# Ucus_Kontrol_Bilgisayari.net
KiCad netlist of a schematic drawn in Altium Designer
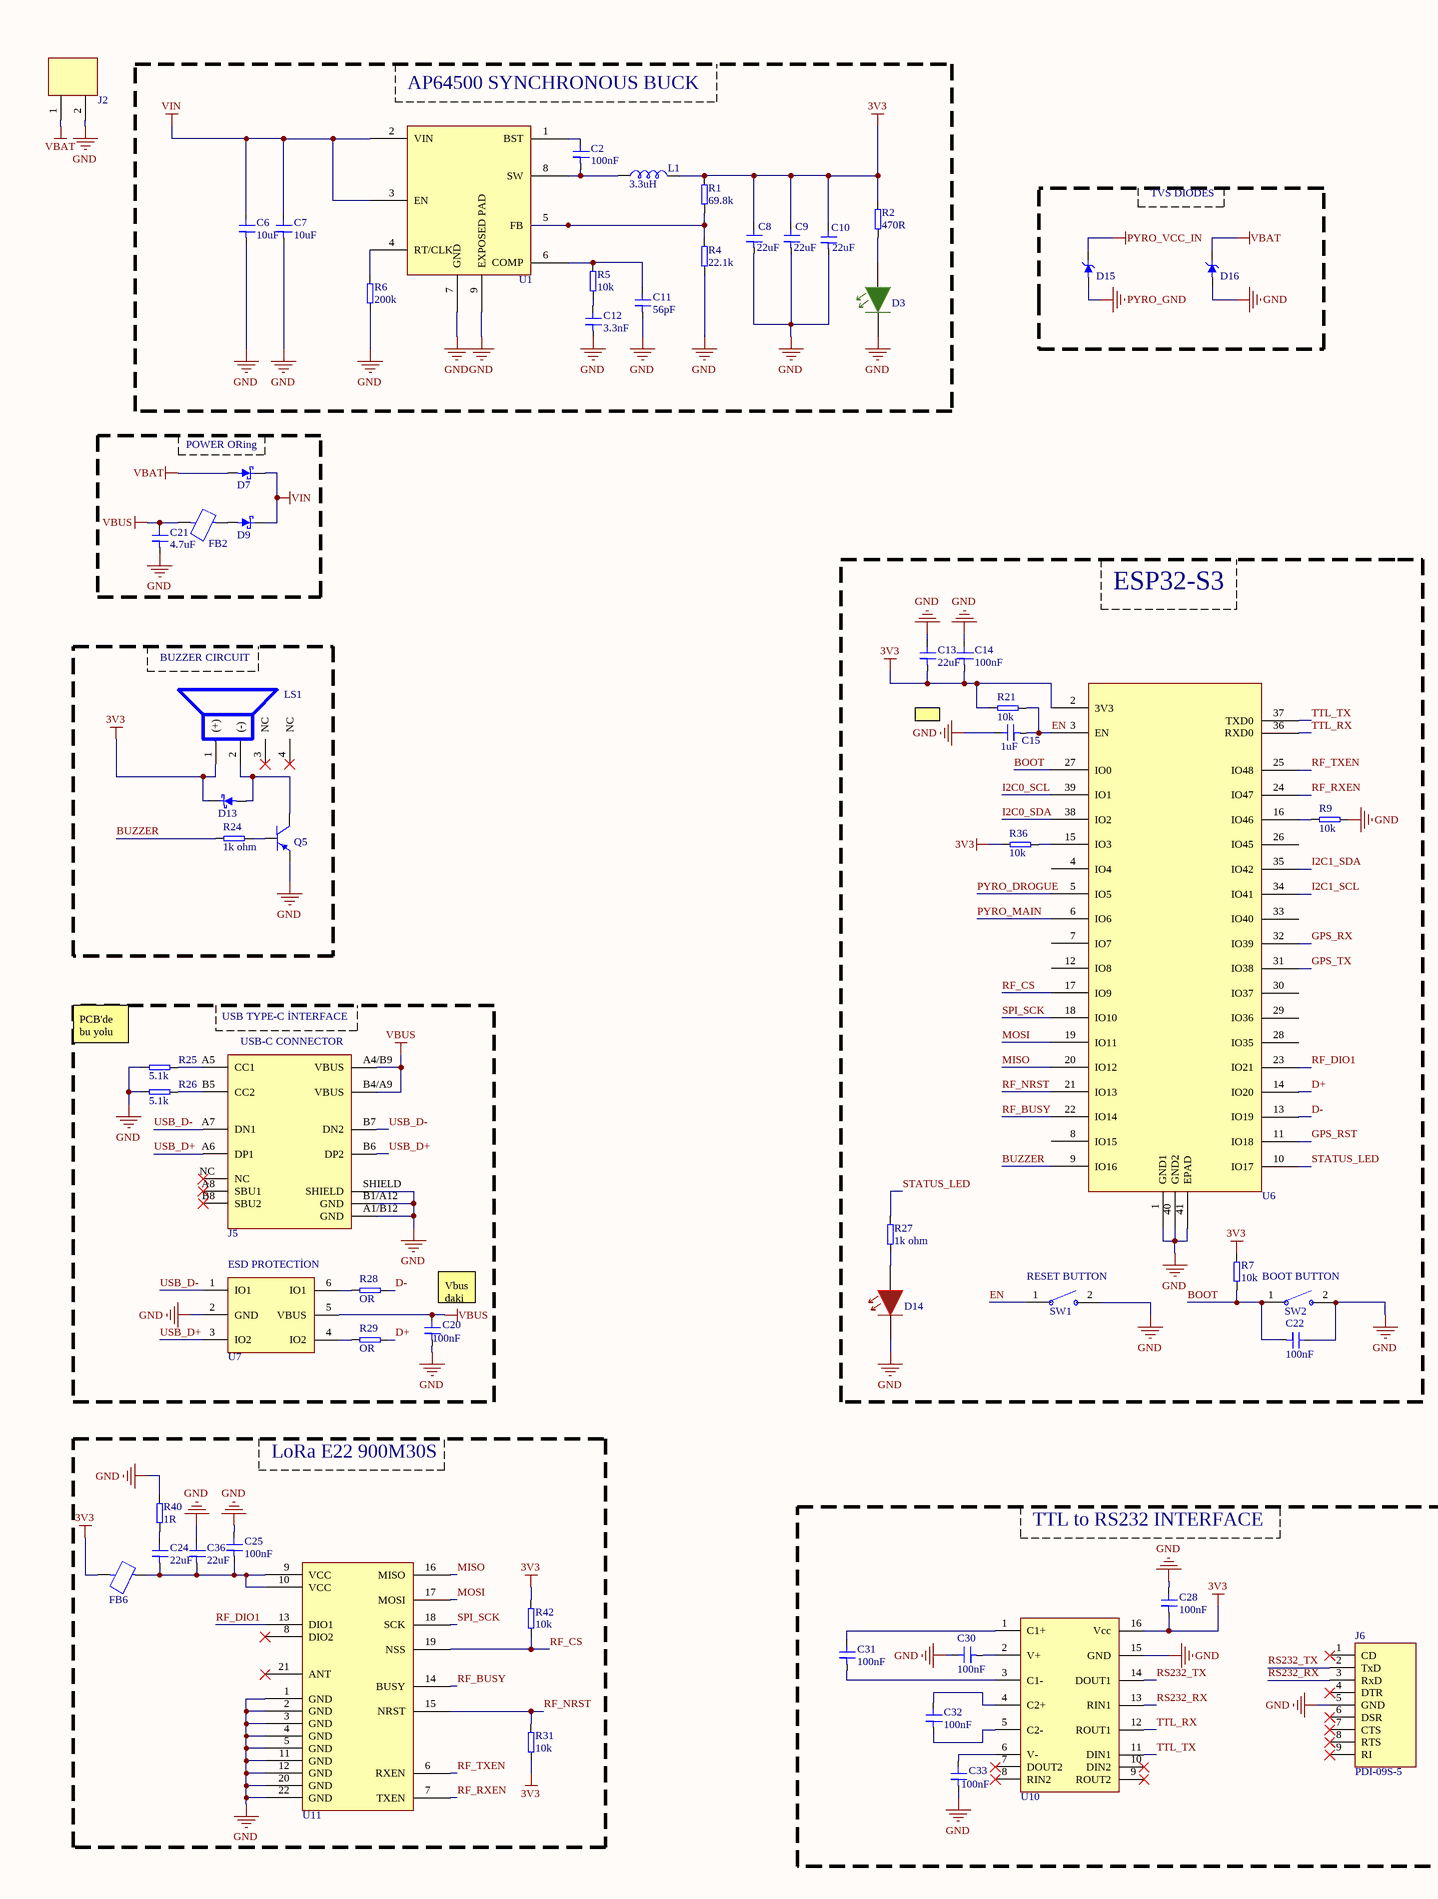
[diagram p0: Ucus_Kontrol_Bilgisayari.SchDoc, left]
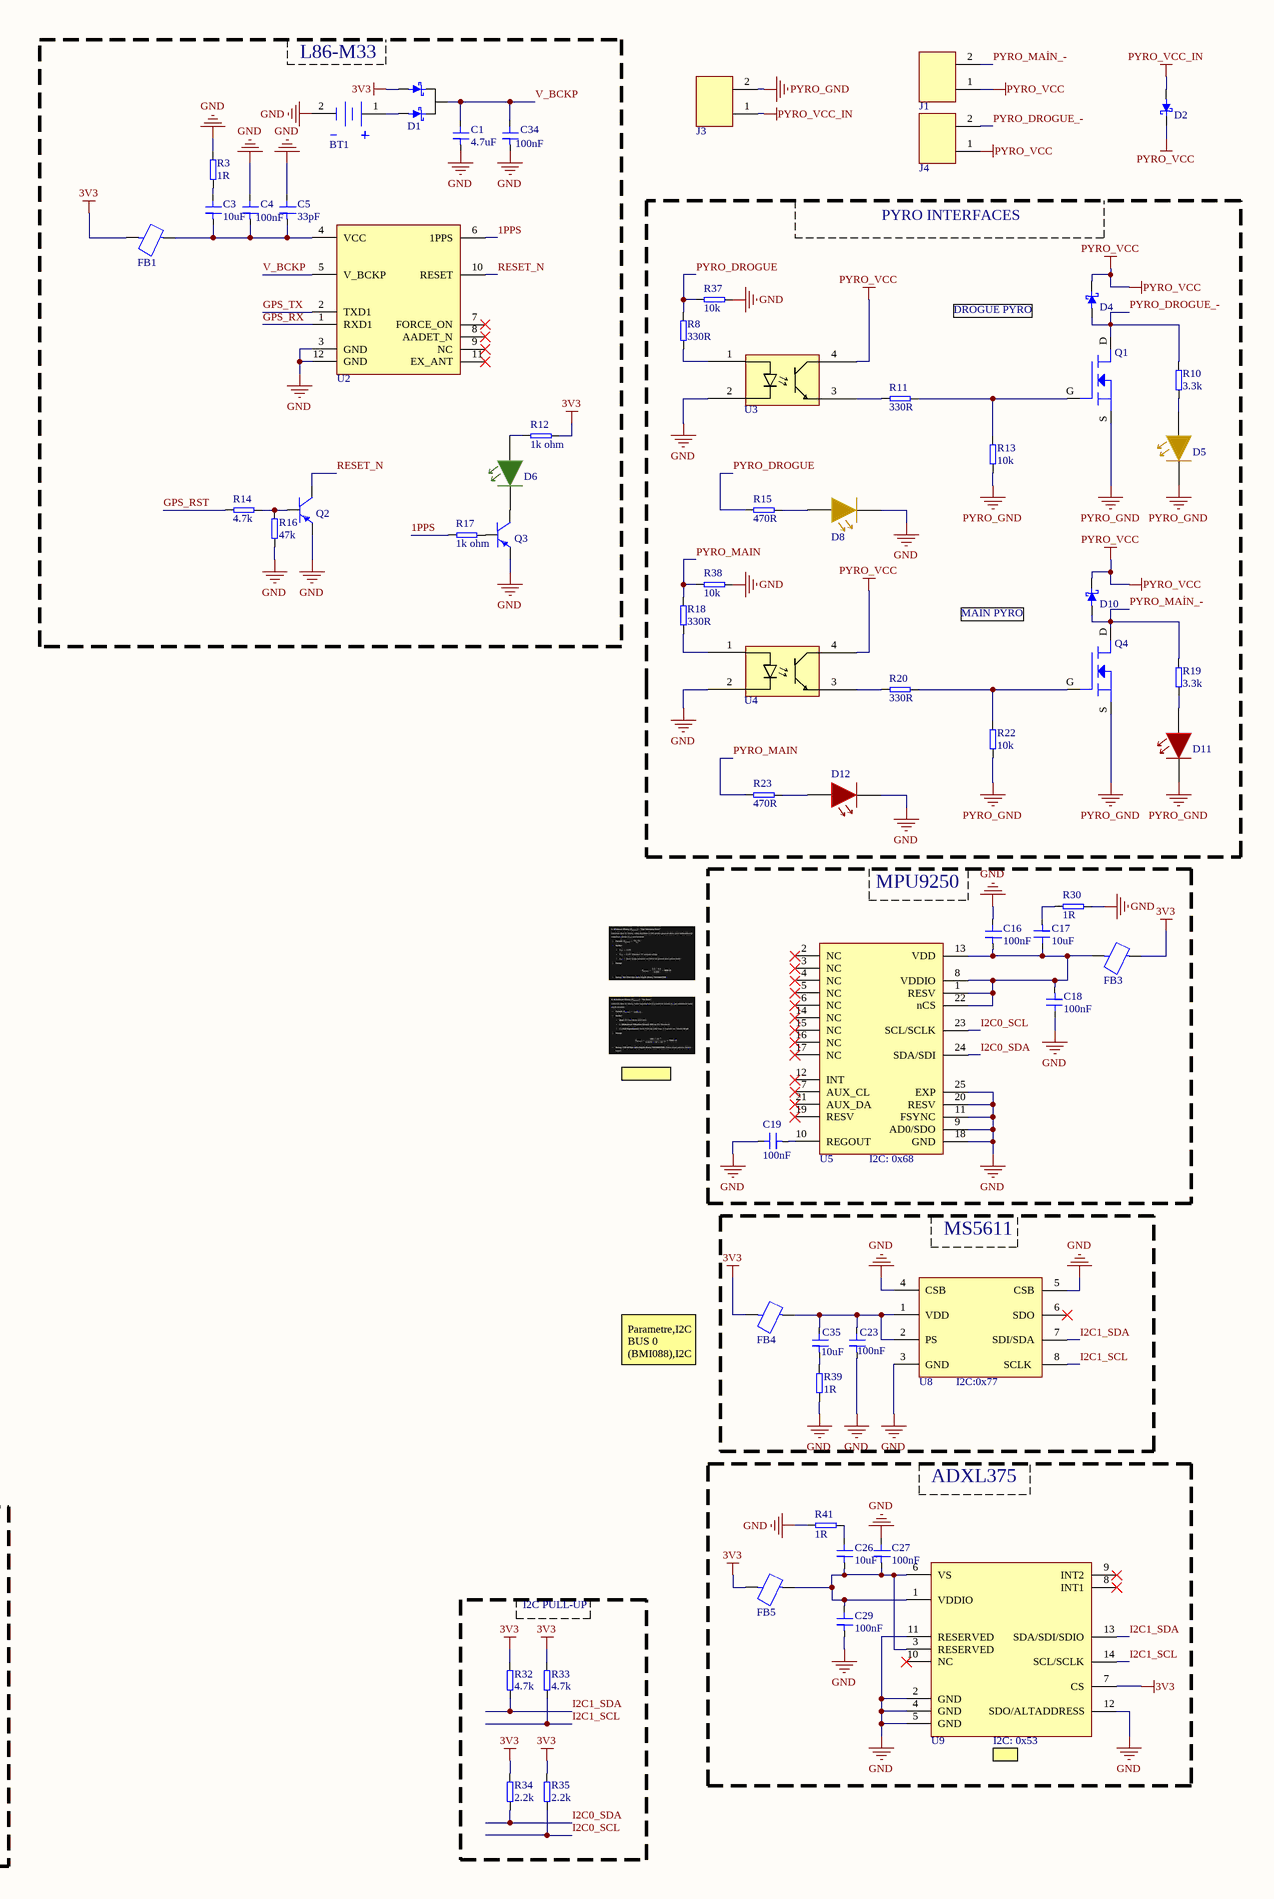
[diagram p1: Ucus_Kontrol_Bilgisayari.SchDoc, right]

(export (version "E")
  (design (tool "Eeschema 10.0.6"))
  (components
    (comp (ref "BT1")
      (value "R2032-1F2DV - 3V Li-MnO2")
      (footprint "CR2032")
      (description "Power-Xtra CR2032-1F2DV - 3V Li-MnO2 - Lithium Buton Pil - 2 Pinli - Dikey")
      (libsource (lib "Electromechanical") (part "CR2032-1F2DV"))
    )
    (comp (ref "C1")
      (value "4.7uF")
      (footprint "0603 CAP SER")
      (fields
        (field (name "MANUFACTURER") "Samsung Electro-Mechanics")
        (field (name "MANUFACTURER PART NUMBER") "CL10A475KO8NNNC")
        (field (name "TOLERANCE") "10%")
      )
      (libsource (lib "Passive") (part "Cap Cer 4.7uF %10 SMD 0603"))
    )
    (comp (ref "C2")
      (value "100nF")
      (footprint "0603 CAP SER")
      (fields
        (field (name "MANUFACTURER") "KEMET")
        (field (name "MANUFACTURER PART NUMBER") "C0603C104J5RAC7867")
        (field (name "DESIGNED BY") "Eren/Mehmet")
      )
      (libsource (lib "Passive") (part "Cap Cer 0.1uF %10 SMD 0603"))
    )
    (comp (ref "C3")
      (value "10uF")
      (footprint "0805 CAP SER")
      (fields
        (field (name "MANUFACTURER") "Samsung")
        (field (name "MANUFACTURER PART NUMBER") "CL21B106KOQNNNE")
        (field (name "DESIGNED BY") "Eren/Mehmet")
      )
      (libsource (lib "Passive") (part "Cap Cer 10uF %10 SMD 0805"))
    )
    (comp (ref "C4")
      (value "100nF")
      (footprint "0603 CAP SER")
      (fields
        (field (name "MANUFACTURER") "KEMET")
        (field (name "MANUFACTURER PART NUMBER") "C0603C104J5RAC7867")
        (field (name "DESIGNED BY") "Eren/Mehmet")
      )
      (libsource (lib "Passive") (part "Cap Cer 0.1uF %10 SMD 0603"))
    )
    (comp (ref "C5")
      (value "33pF")
      (footprint "0603 CAP SER")
      (description "50V 33pF NP0 ±5% 0603 Multilayer Ceramic Capacitors MLCC - SMD/SMT ROHS")
      (fields
        (field (name "MANUFACTURER") "Yageo Group")
        (field (name "MANUFACTURER PART NUMBER") "CC0603JRNPO9BN330")
      )
      (libsource (lib "Passive") (part "Cap Cer 33pF %5 SMD 0603"))
    )
    (comp (ref "C6")
      (value "10uF")
      (footprint "1206 CAP SER")
      (fields
        (field (name "MANUFACTURER") "Samsung Electro-Mechanics")
        (field (name "MANUFACTURER PART NUMBER") "CL31B106KAHNNNE")
        (field (name "TOLERANCE") "10%")
      )
      (libsource (lib "Passive") (part "Cap Cer 10uF %10 SMD 1206 (25V)"))
    )
    (comp (ref "C7")
      (value "10uF")
      (footprint "1206 CAP SER")
      (fields
        (field (name "MANUFACTURER") "Samsung Electro-Mechanics")
        (field (name "MANUFACTURER PART NUMBER") "CL31B106KAHNNNE")
        (field (name "TOLERANCE") "10%")
      )
      (libsource (lib "Passive") (part "Cap Cer 10uF %10 SMD 1206 (25V)"))
    )
    (comp (ref "C8")
      (value "22uF")
      (footprint "1206 CAP SER")
      (fields
        (field (name "MANUFACTURER") "Samsung")
        (field (name "MANUFACTURER PART NUMBER") "CL31B226KPHNNNE")
        (field (name "DESIGNED BY") "Eren/Mehmet")
      )
      (libsource (lib "Passive") (part "Cap Cer 22uF %10 SMD 1206"))
    )
    (comp (ref "C9")
      (value "22uF")
      (footprint "1206 CAP SER")
      (fields
        (field (name "MANUFACTURER") "Samsung")
        (field (name "MANUFACTURER PART NUMBER") "CL31B226KPHNNNE")
        (field (name "DESIGNED BY") "Eren/Mehmet")
      )
      (libsource (lib "Passive") (part "Cap Cer 22uF %10 SMD 1206"))
    )
    (comp (ref "C10")
      (value "22uF")
      (footprint "1206 CAP SER")
      (fields
        (field (name "MANUFACTURER") "Samsung")
        (field (name "MANUFACTURER PART NUMBER") "CL31B226KPHNNNE")
        (field (name "DESIGNED BY") "Eren/Mehmet")
      )
      (libsource (lib "Passive") (part "Cap Cer 22uF %10 SMD 1206"))
    )
    (comp (ref "C11")
      (value "56pF")
      (footprint "0603 CAP SER")
      (description "Multilayer Ceramic Capacitor, 56 pF, 50 V, ± 5%, C0G (NP0), 0603 [1608 Metric]")
      (fields
        (field (name "MANUFACTURER") "Samsung Electro-Mechanics")
        (field (name "MANUFACTURER PART NUMBER") "CL10C560JB8NNNC")
      )
      (libsource (lib "Passive") (part "Cap Cer 56pF %5 SMD 0603"))
    )
    (comp (ref "C12")
      (value "3.3nF")
      (footprint "0603 CAP SER")
      (fields
        (field (name "MANUFACTURER") "Samsung Electro-Mechanics")
        (field (name "MANUFACTURER PART NUMBER") "CL10B332KB8NNNC")
        (field (name "TOLERANCE") "10%")
      )
      (libsource (lib "Passive") (part "Cap Cer 3.3nF %10 SMD 0603"))
    )
    (comp (ref "C13")
      (value "22uF")
      (footprint "1206 CAP SER")
      (fields
        (field (name "MANUFACTURER") "Samsung")
        (field (name "MANUFACTURER PART NUMBER") "CL31B226KPHNNNE")
        (field (name "DESIGNED BY") "Eren/Mehmet")
      )
      (libsource (lib "Passive") (part "Cap Cer 22uF %10 SMD 1206"))
    )
    (comp (ref "C14")
      (value "100nF")
      (footprint "0603 CAP SER")
      (fields
        (field (name "MANUFACTURER") "KEMET")
        (field (name "MANUFACTURER PART NUMBER") "C0603C104J5RAC7867")
        (field (name "DESIGNED BY") "Eren/Mehmet")
      )
      (libsource (lib "Passive") (part "Cap Cer 0.1uF %10 SMD 0603"))
    )
    (comp (ref "C15")
      (value "1uF")
      (footprint "0603 CAP SER")
      (fields
        (field (name "MANUFACTURER") "Samsung Electro-Mechanics")
        (field (name "MANUFACTURER PART NUMBER") "CL10B105KO8NNNC")
        (field (name "TOLERANCE") "10%")
      )
      (libsource (lib "Passive") (part "Cap Cer 1uF %10 SMD 0603"))
    )
    (comp (ref "C16")
      (value "100nF")
      (footprint "0603 CAP SER")
      (fields
        (field (name "MANUFACTURER") "KEMET")
        (field (name "MANUFACTURER PART NUMBER") "C0603C104J5RAC7867")
        (field (name "DESIGNED BY") "Eren/Mehmet")
      )
      (libsource (lib "Passive") (part "Cap Cer 0.1uF %10 SMD 0603"))
    )
    (comp (ref "C17")
      (value "10uF")
      (footprint "0805 CAP SER")
      (fields
        (field (name "MANUFACTURER") "Samsung")
        (field (name "MANUFACTURER PART NUMBER") "CL21B106KOQNNNE")
        (field (name "DESIGNED BY") "Eren/Mehmet")
      )
      (libsource (lib "Passive") (part "Cap Cer 10uF %10 SMD 0805"))
    )
    (comp (ref "C18")
      (value "100nF")
      (footprint "0603 CAP SER")
      (fields
        (field (name "MANUFACTURER") "KEMET")
        (field (name "MANUFACTURER PART NUMBER") "C0603C104J5RAC7867")
        (field (name "DESIGNED BY") "Eren/Mehmet")
      )
      (libsource (lib "Passive") (part "Cap Cer 0.1uF %10 SMD 0603"))
    )
    (comp (ref "C19")
      (value "100nF")
      (footprint "0603 CAP SER")
      (fields
        (field (name "MANUFACTURER") "KEMET")
        (field (name "MANUFACTURER PART NUMBER") "C0603C104J5RAC7867")
        (field (name "DESIGNED BY") "Eren/Mehmet")
      )
      (libsource (lib "Passive") (part "Cap Cer 0.1uF %10 SMD 0603"))
    )
    (comp (ref "C20")
      (value "100nF")
      (footprint "0603 CAP SER")
      (fields
        (field (name "MANUFACTURER") "KEMET")
        (field (name "MANUFACTURER PART NUMBER") "C0603C104J5RAC7867")
        (field (name "DESIGNED BY") "Eren/Mehmet")
      )
      (libsource (lib "Passive") (part "Cap Cer 0.1uF %10 SMD 0603"))
    )
    (comp (ref "C21")
      (value "4.7uF")
      (footprint "0805 CAP SER")
      (fields
        (field (name "MANUFACTURER") "Samsung Electro-Mechanics")
        (field (name "MANUFACTURER PART NUMBER") "CL21B475KOQVPNE")
        (field (name "TOLERANCE") "10%")
      )
      (libsource (lib "Passive") (part "Cap Cer 4.7uF %10 SMD 0805"))
    )
    (comp (ref "C22")
      (value "100nF")
      (footprint "0603 CAP SER")
      (fields
        (field (name "MANUFACTURER") "KEMET")
        (field (name "MANUFACTURER PART NUMBER") "C0603C104J5RAC7867")
        (field (name "DESIGNED BY") "Eren/Mehmet")
      )
      (libsource (lib "Passive") (part "Cap Cer 0.1uF %10 SMD 0603"))
    )
    (comp (ref "C23")
      (value "100nF")
      (footprint "0603 CAP SER")
      (fields
        (field (name "MANUFACTURER") "KEMET")
        (field (name "MANUFACTURER PART NUMBER") "C0603C104J5RAC7867")
        (field (name "DESIGNED BY") "Eren/Mehmet")
      )
      (libsource (lib "Passive") (part "Cap Cer 0.1uF %10 SMD 0603"))
    )
    (comp (ref "C24")
      (value "22uF")
      (footprint "1206 CAP SER")
      (fields
        (field (name "MANUFACTURER") "Samsung")
        (field (name "MANUFACTURER PART NUMBER") "CL31B226KPHNNNE")
        (field (name "DESIGNED BY") "Eren/Mehmet")
      )
      (libsource (lib "Passive") (part "Cap Cer 22uF %10 SMD 1206"))
    )
    (comp (ref "C25")
      (value "100nF")
      (footprint "0603 CAP SER")
      (fields
        (field (name "MANUFACTURER") "KEMET")
        (field (name "MANUFACTURER PART NUMBER") "C0603C104J5RAC7867")
        (field (name "DESIGNED BY") "Eren/Mehmet")
      )
      (libsource (lib "Passive") (part "Cap Cer 0.1uF %10 SMD 0603"))
    )
    (comp (ref "C26")
      (value "10uF")
      (footprint "0805 CAP SER")
      (fields
        (field (name "MANUFACTURER") "Samsung")
        (field (name "MANUFACTURER PART NUMBER") "CL21B106KOQNNNE")
        (field (name "DESIGNED BY") "Eren/Mehmet")
      )
      (libsource (lib "Passive") (part "Cap Cer 10uF %10 SMD 0805"))
    )
    (comp (ref "C27")
      (value "100nF")
      (footprint "0603 CAP SER")
      (fields
        (field (name "MANUFACTURER") "KEMET")
        (field (name "MANUFACTURER PART NUMBER") "C0603C104J5RAC7867")
        (field (name "DESIGNED BY") "Eren/Mehmet")
      )
      (libsource (lib "Passive") (part "Cap Cer 0.1uF %10 SMD 0603"))
    )
    (comp (ref "C28")
      (value "100nF")
      (footprint "0603 CAP SER")
      (fields
        (field (name "MANUFACTURER") "KEMET")
        (field (name "MANUFACTURER PART NUMBER") "C0603C104J5RAC7867")
        (field (name "DESIGNED BY") "Eren/Mehmet")
      )
      (libsource (lib "Passive") (part "Cap Cer 0.1uF %10 SMD 0603"))
    )
    (comp (ref "C29")
      (value "100nF")
      (footprint "0603 CAP SER")
      (fields
        (field (name "MANUFACTURER") "KEMET")
        (field (name "MANUFACTURER PART NUMBER") "C0603C104J5RAC7867")
        (field (name "DESIGNED BY") "Eren/Mehmet")
      )
      (libsource (lib "Passive") (part "Cap Cer 0.1uF %10 SMD 0603"))
    )
    (comp (ref "C30")
      (value "100nF")
      (footprint "0603 CAP SER")
      (fields
        (field (name "MANUFACTURER") "KEMET")
        (field (name "MANUFACTURER PART NUMBER") "C0603C104J5RAC7867")
        (field (name "DESIGNED BY") "Eren/Mehmet")
      )
      (libsource (lib "Passive") (part "Cap Cer 0.1uF %10 SMD 0603"))
    )
    (comp (ref "C31")
      (value "100nF")
      (footprint "0603 CAP SER")
      (fields
        (field (name "MANUFACTURER") "KEMET")
        (field (name "MANUFACTURER PART NUMBER") "C0603C104J5RAC7867")
        (field (name "DESIGNED BY") "Eren/Mehmet")
      )
      (libsource (lib "Passive") (part "Cap Cer 0.1uF %10 SMD 0603"))
    )
    (comp (ref "C32")
      (value "100nF")
      (footprint "0603 CAP SER")
      (fields
        (field (name "MANUFACTURER") "KEMET")
        (field (name "MANUFACTURER PART NUMBER") "C0603C104J5RAC7867")
        (field (name "DESIGNED BY") "Eren/Mehmet")
      )
      (libsource (lib "Passive") (part "Cap Cer 0.1uF %10 SMD 0603"))
    )
    (comp (ref "C33")
      (value "100nF")
      (footprint "0603 CAP SER")
      (fields
        (field (name "MANUFACTURER") "KEMET")
        (field (name "MANUFACTURER PART NUMBER") "C0603C104J5RAC7867")
        (field (name "DESIGNED BY") "Eren/Mehmet")
      )
      (libsource (lib "Passive") (part "Cap Cer 0.1uF %10 SMD 0603"))
    )
    (comp (ref "C34")
      (value "100nF")
      (footprint "0603 CAP SER")
      (fields
        (field (name "MANUFACTURER") "KEMET")
        (field (name "MANUFACTURER PART NUMBER") "C0603C104J5RAC7867")
        (field (name "DESIGNED BY") "Eren/Mehmet")
      )
      (libsource (lib "Passive") (part "Cap Cer 0.1uF %10 SMD 0603"))
    )
    (comp (ref "C35")
      (value "10uF")
      (footprint "0805 CAP SER")
      (fields
        (field (name "MANUFACTURER") "Samsung")
        (field (name "MANUFACTURER PART NUMBER") "CL21B106KOQNNNE")
        (field (name "DESIGNED BY") "Eren/Mehmet")
      )
      (libsource (lib "Passive") (part "Cap Cer 10uF %10 SMD 0805"))
    )
    (comp (ref "C36")
      (value "22uF")
      (footprint "1206 CAP SER")
      (fields
        (field (name "MANUFACTURER") "Samsung")
        (field (name "MANUFACTURER PART NUMBER") "CL31B226KPHNNNE")
        (field (name "DESIGNED BY") "Eren/Mehmet")
      )
      (libsource (lib "Passive") (part "Cap Cer 22uF %10 SMD 1206"))
    )
    (comp (ref "D1")
      (value "DIODE SCHOTTKY 2*0.2A 30V SOT23 CATHODE LRC")
      (footprint "SOT-23")
      (description "BAT54C Series 30 V 200 mA SMT Small Signal Schottky Diode - SOT-23-3")
      (fields (field (name "MANUFACTURER") "Vishay") (field (name "MANUFACTURER PART NUMBER") "LBAT54CLT1G"))
      (libsource (lib "Active") (part "LBAT54CLT1G"))
    )
    (comp (ref "D2")
      (value "Low VF Schottky Rect.")
      (footprint "DO214AA (SMB)")
      (description "DIODE SCHOTTKY 5A 40V DO214AA (SMB) SMT")
      (libsource (lib "Active") (part "SK54BL_R2_00001"))
    )
    (comp (ref "D3")
      (value "LED SMD 0805 GREEN 18-45mcd 140° WATER CLEAR")
      (footprint "LED 0805 GREEN")
      (description "Single Color LED, Brilliant Yellow Green, Water Clear, 1.4mm")
      (fields
        (field (name "MANUFACTURER") "Everlight")
        (field (name "MANUFACTURER PART NUMBER") "17-21/G6C-FM1N2B/4T")
      )
      (libsource (lib "Active") (part "LED GREEN 0805"))
    )
    (comp (ref "D4")
      (value "DIODE SCHOTTKY 1A 40V SOD123 SMT")
      (footprint "SOD-123")
      (description "Rectifier Diode, Schottky, 1 Phase, 1 Element, 1A, 40V V(RRM), Silicon")
      (fields
        (field (name "MANUFACTURER") "Panjit")
        (field (name "MANUFACTURER PART NUMBER") "SS1040L_R1_00001")
      )
      (libsource (lib "Active") (part "SS1040L_R1_00001"))
    )
    (comp (ref "D5")
      (value "LED SMD 0805 YELLOW 28.5-72mcd 140° WATER CLEAR")
      (footprint "LED 0805 YELLOW")
      (description "Single Color LED, Brilliant Yellow, Water Clear, 1.4mm")
      (fields
        (field (name "MANUFACTURER") "Everlight")
        (field (name "MANUFACTURER PART NUMBER") "17-21/Y2C-AN1P2/4T")
      )
      (libsource (lib "Active") (part "LED YELLOW 0805"))
    )
    (comp (ref "D6")
      (value "LED SMD 0805 GREEN 18-45mcd 140° WATER CLEAR")
      (footprint "LED 0805 GREEN")
      (description "Single Color LED, Brilliant Yellow Green, Water Clear, 1.4mm")
      (fields
        (field (name "MANUFACTURER") "Everlight")
        (field (name "MANUFACTURER PART NUMBER") "17-21/G6C-FM1N2B/4T")
      )
      (libsource (lib "Active") (part "LED GREEN 0805"))
    )
    (comp (ref "D7")
      (value "DIODE SCHOTTKY 3A 30V DO214AC (SMA) SMT")
      (footprint "DO-214AC 1F")
      (description "30V, 3A, SMD Schottky Barrier Diode with 60A Surge; 1F Package Type")
      (fields
        (field (name "MANUFACTURER") "Shindengen")
        (field (name "MANUFACTURER PART NUMBER") "D1FH3-5053")
      )
      (libsource (lib "Active") (part "D1FH3-5053"))
    )
    (comp (ref "D8")
      (value "LED SMD 0805 YELLOW 28.5-72mcd 140° WATER CLEAR")
      (footprint "LED 0805 YELLOW")
      (description "Single Color LED, Brilliant Yellow, Water Clear, 1.4mm")
      (fields
        (field (name "MANUFACTURER") "Everlight")
        (field (name "MANUFACTURER PART NUMBER") "17-21/Y2C-AN1P2/4T")
      )
      (libsource (lib "Active") (part "LED YELLOW 0805"))
    )
    (comp (ref "D9")
      (value "DIODE SCHOTTKY 3A 30V DO214AC (SMA) SMT")
      (footprint "DO-214AC 1F")
      (description "30V, 3A, SMD Schottky Barrier Diode with 60A Surge; 1F Package Type")
      (fields
        (field (name "MANUFACTURER") "Shindengen")
        (field (name "MANUFACTURER PART NUMBER") "D1FH3-5053")
      )
      (libsource (lib "Active") (part "D1FH3-5053"))
    )
    (comp (ref "D10")
      (value "DIODE SCHOTTKY 1A 40V SOD123 SMT")
      (footprint "SOD-123")
      (description "Rectifier Diode, Schottky, 1 Phase, 1 Element, 1A, 40V V(RRM), Silicon")
      (fields
        (field (name "MANUFACTURER") "Panjit")
        (field (name "MANUFACTURER PART NUMBER") "SS1040L_R1_00001")
      )
      (libsource (lib "Active") (part "SS1040L_R1_00001"))
    )
    (comp (ref "D11")
      (value "LED SMD 0805 RED 45~112mcd 120C")
      (footprint "LED 0805 RED")
      (description "Single Color LED, Brilliant Red, Water Clear, 1.4mm")
      (fields
        (field (name "MANUFACTURER") "Everlight")
        (field (name "MANUFACTURER PART NUMBER") "17-21/R6C-AP1Q2L/4T")
      )
      (libsource (lib "Active") (part "LED RED 0805"))
    )
    (comp (ref "D12")
      (value "LED SMD 0805 RED 45~112mcd 120C")
      (footprint "LED 0805 RED")
      (description "Single Color LED, Brilliant Red, Water Clear, 1.4mm")
      (fields
        (field (name "MANUFACTURER") "Everlight")
        (field (name "MANUFACTURER PART NUMBER") "17-21/R6C-AP1Q2L/4T")
      )
      (libsource (lib "Active") (part "LED RED 0805"))
    )
    (comp (ref "D13")
      (value "DIODE SCHOTTKY 1A 40V SOD123 SMT")
      (footprint "SOD-123")
      (description "Rectifier Diode, Schottky, 1 Phase, 1 Element, 1A, 40V V(RRM), Silicon")
      (fields
        (field (name "MANUFACTURER") "Panjit")
        (field (name "MANUFACTURER PART NUMBER") "SS1040L_R1_00001")
      )
      (libsource (lib "Active") (part "SS1040L_R1_00001"))
    )
    (comp (ref "D14")
      (value "LED SMD 0805 RED 45~112mcd 120C")
      (footprint "LED 0805 RED")
      (description "Single Color LED, Brilliant Red, Water Clear, 1.4mm")
      (fields
        (field (name "MANUFACTURER") "Everlight")
        (field (name "MANUFACTURER PART NUMBER") "17-21/R6C-AP1Q2L/4T")
      )
      (libsource (lib "Active") (part "LED RED 0805"))
    )
    (comp (ref "D15")
      (value "DIODE TVS 1500W 14V DO214AB (SMC) SMT")
      (footprint "DO214AB (SMC)")
      (libsource (lib "Active") (part "1.5SMCJ14A_R2_00001"))
    )
    (comp (ref "D16")
      (value "DIODE TVS 600W 10V DO214AA (SMB) SMT")
      (footprint "DO214AA (SMB)")
      (description "Trans Voltage Suppressor Diode, 600W, 10V V(RWM), Unidirectional, 1 Element, Silicon")
      (fields
        (field (name "MANUFACTURER") "Panjit")
        (field (name "MANUFACTURER PART NUMBER") "P6SMBJ10AS_R1_00001")
      )
      (libsource (lib "Active") (part "P6SMBJ10AS_R1_00001"))
    )
    (comp (ref "FB1")
      (value "FERRİTE BEADS 600 OHM POWER MURATA")
      (footprint "0603 FERRİT BEAD")
      (description "Ferrite Beads Multi-Layer 600Ohm 25% 100MHz 500mA 350mOhm DCR 0603 Paper T/R")
      (fields
        (field (name "MANUFACTURER") "Murata")
        (field (name "MANUFACTURER PART NUMBER") "BLM18EG601SN1D")
      )
      (libsource (lib "Passive") (part "FERRİTE BEAD 0603 600R"))
    )
    (comp (ref "FB2")
      (value "FERRITE BEAD 0805 180R 4A SMD")
      (footprint "0805 FERRİT BEAD")
      (description "Ferrite Beads Multi-Layer Power 180Ohm 25% 100MHz 4A 0.02Ohm DCR 0805 T/R Automotive AEC-Q200")
      (fields
        (field (name "MANUFACTURER") "Murata")
        (field (name "MANUFACTURER PART NUMBER") "BLM21SP181SZ1D")
      )
      (libsource (lib "Passive") (part "FERRİTE BEAD 0805 180R 4A"))
    )
    (comp (ref "FB3")
      (value "FERRİTE BEADS 600 OHM POWER MURATA")
      (footprint "0603 FERRİT BEAD")
      (description "Ferrite Beads Multi-Layer 600Ohm 25% 100MHz 500mA 350mOhm DCR 0603 Paper T/R")
      (fields
        (field (name "MANUFACTURER") "Murata")
        (field (name "MANUFACTURER PART NUMBER") "BLM18EG601SN1D")
      )
      (libsource (lib "Passive") (part "FERRİTE BEAD 0603 600R"))
    )
    (comp (ref "FB4")
      (value "FERRİTE BEADS 600 OHM POWER MURATA")
      (footprint "0603 FERRİT BEAD")
      (description "Ferrite Beads Multi-Layer 600Ohm 25% 100MHz 500mA 350mOhm DCR 0603 Paper T/R")
      (fields
        (field (name "MANUFACTURER") "Murata")
        (field (name "MANUFACTURER PART NUMBER") "BLM18EG601SN1D")
      )
      (libsource (lib "Passive") (part "FERRİTE BEAD 0603 600R"))
    )
    (comp (ref "FB5")
      (value "FERRİTE BEADS 600 OHM POWER MURATA")
      (footprint "0603 FERRİT BEAD")
      (description "Ferrite Beads Multi-Layer 600Ohm 25% 100MHz 500mA 350mOhm DCR 0603 Paper T/R")
      (fields
        (field (name "MANUFACTURER") "Murata")
        (field (name "MANUFACTURER PART NUMBER") "BLM18EG601SN1D")
      )
      (libsource (lib "Passive") (part "FERRİTE BEAD 0603 600R"))
    )
    (comp (ref "FB6")
      (value "FERRITE BEAD 0805 180R 4A SMD")
      (footprint "0805 FERRİT BEAD")
      (description "Ferrite Beads Multi-Layer Power 180Ohm 25% 100MHz 4A 0.02Ohm DCR 0805 T/R Automotive AEC-Q200")
      (fields
        (field (name "MANUFACTURER") "Murata")
        (field (name "MANUFACTURER PART NUMBER") "BLM21SP181SZ1D")
      )
      (libsource (lib "Passive") (part "FERRİTE BEAD 0805 180R 4A"))
    )
    (comp (ref "J1")
      (value "XT30 Konnektör")
      (footprint "XT30")
      (libsource (lib "Electromechanical") (part "XT30"))
    )
    (comp (ref "J2") (value "XT30 Konnektör") (footprint "XT30") (libsource (lib "") (part "XT30_1")))
    (comp (ref "J3")
      (value "XT30 Konnektör")
      (footprint "XT30")
      (libsource (lib "Electromechanical") (part "XT30"))
    )
    (comp (ref "J4")
      (value "XT30 Konnektör")
      (footprint "XT30")
      (libsource (lib "Electromechanical") (part "XT30"))
    )
    (comp (ref "J5")
      (value "CONNECTOR USB C R/A TYPE 16P")
      (footprint "USB4105-GF-A")
      (description "USB Connector, 24 Contact(s), Female, Right Angle, Solder Terminal, Locking, Receptacle")
      (fields
        (field (name "MANUFACTURER") "Global Connector Technology")
        (field (name "MANUFACTURER PART NUMBER") "USB4105-GF-A")
      )
      (libsource (lib "Electromechanical") (part "USB4105-GF-A"))
    )
    (comp (ref "J6")
      (value "PDI-09S-5")
      (footprint "PDI-09R-5")
      (description "Right Angle, P.C.B., 5.0mm Footprint")
      (libsource (lib "Electromechanical") (part "PDI-09S-5"))
    )
    (comp (ref "L1")
      (value "3.3uH")
      (footprint "SRP7030-3R3M")
      (description "Inductor Power Shielded Wirewound 3.3uH 20% 100KHz Iron 6A 0.03Ohm DCR T/R")
      (fields (field (name "MANUFACTURER") "Bourns") (field (name "MANUFACTURER PART NUMBER") "SRP7030-3R3M"))
      (libsource (lib "Passive") (part "INDUCTOR 3.3uH 6A 20mOhm SMD"))
    )
    (comp (ref "LS1")
      (value "BUZZER MAGNETIC W/O CIRCUIT 3.6V 2.31-KHZ SMT")
      (footprint "MTS7525A04LM")
      (libsource (lib "Electromechanical") (part "MTS7525A04LM"))
    )
    (comp (ref "Q1")
      (value "MOSFET DIS.84A 25V N-CH TDSON-8 OPTIMOS SMT")
      (footprint "PG-TDSON-8")
      (description "Transistor: N-MOSFET; unipolar; 25V; 84A; 37W; PG-TDSON-8")
      (fields
        (field (name "MANUFACTURER") "Infineon")
        (field (name "MANUFACTURER PART NUMBER") "BSC032NE2LSATMA1")
      )
      (libsource (lib "Active") (part "BSC032NE2LSATMA1"))
    )
    (comp (ref "Q2")
      (value "TRANSISTOR DIS.600mA 40V NPN SOT23 GEN. SMT")
      (footprint "SOT-23")
      (description "Trans Gp Bjt NPN 40V 0.6A 350MW 3-PIN SOT-23 T/r")
      (fields (field (name "MANUFACTURER") "MCC") (field (name "MANUFACTURER PART NUMBER") "MMBT4401-TP"))
      (libsource (lib "Active") (part "MMBT4401-TP"))
    )
    (comp (ref "Q3")
      (value "TRANSISTOR DIS.600mA 40V NPN SOT23 GEN. SMT")
      (footprint "SOT-23")
      (description "Trans Gp Bjt NPN 40V 0.6A 350MW 3-PIN SOT-23 T/r")
      (fields (field (name "MANUFACTURER") "MCC") (field (name "MANUFACTURER PART NUMBER") "MMBT4401-TP"))
      (libsource (lib "Active") (part "MMBT4401-TP"))
    )
    (comp (ref "Q4")
      (value "MOSFET DIS.84A 25V N-CH TDSON-8 OPTIMOS SMT")
      (footprint "PG-TDSON-8")
      (description "Transistor: N-MOSFET; unipolar; 25V; 84A; 37W; PG-TDSON-8")
      (fields
        (field (name "MANUFACTURER") "Infineon")
        (field (name "MANUFACTURER PART NUMBER") "BSC032NE2LSATMA1")
      )
      (libsource (lib "Active") (part "BSC032NE2LSATMA1"))
    )
    (comp (ref "Q5")
      (value "TRANSISTOR DIS.600mA 40V NPN SOT23 GEN. SMT")
      (footprint "SOT-23")
      (description "Trans Gp Bjt NPN 40V 0.6A 350MW 3-PIN SOT-23 T/r")
      (fields (field (name "MANUFACTURER") "MCC") (field (name "MANUFACTURER PART NUMBER") "MMBT4401-TP"))
      (libsource (lib "Active") (part "MMBT4401-TP"))
    )
    (comp (ref "R1")
      (value "69.8k")
      (footprint "0603 RES")
      (description "RES.(1608) 0603 69.8K Ohms 1% 1/10W-S 100PPM")
      (fields
        (field (name "MANUFACTURER") "Royal Ohm")
        (field (name "MANUFACTURER PART NUMBER") "0603SAF6982T5E")
      )
      (libsource (lib "Passive") (part "RES 69.8kOhm %1 SMD 0603"))
    )
    (comp (ref "R2")
      (value "470R")
      (footprint "0603 RES")
      (description "RES.(1608) 0603 470 Ohms 1% 1/10W AUTOMOTIV")
      (fields
        (field (name "MANUFACTURER") "Royal Ohm")
        (field (name "MANUFACTURER PART NUMBER") "CQ03SAF4700T5E")
      )
      (libsource (lib "Passive") (part "RES  470 Ohm %1 SMD 0603"))
    )
    (comp (ref "R3")
      (value "1R")
      (footprint "0603 RES")
      (description "RES.(1608) 0603 1 Ohms 1% 1/10W AUTOMOTIV")
      (fields
        (field (name "MANUFACTURER") "Royal Ohm")
        (field (name "MANUFACTURER PART NUMBER") "CQ03SAF100KT5E")
      )
      (libsource (lib "Passive") (part "RES 1R Ohm %1 SMD 0603"))
    )
    (comp (ref "R4")
      (value "22.1k")
      (footprint "0603 RES")
      (description "Res Thick Film 0603 22.1K Ohm 1% 0.1W(1/10W) ±100ppm/°C Pad SMD T/R")
      (fields
        (field (name "MANUFACTURER") "Royal Ohm")
        (field (name "MANUFACTURER PART NUMBER") "0603SAF2212T5E")
      )
      (libsource (lib "Passive") (part "RES 22.1K Ohms 1% SMD 0603"))
    )
    (comp (ref "R5")
      (value "10k")
      (footprint "0603 RES")
      (fields
        (field (name "MANUFACTURER") "Yageo")
        (field (name "MANUFACTURER PART NUMBER") "RC0603JR-0710KL")
        (field (name "TOLERANCE") "5%")
        (field (name "DESIGNED BY") "Eren/Mehmet")
      )
      (libsource (lib "Passive") (part "RES 10kOhm %5 SMD 0603"))
    )
    (comp (ref "R6")
      (value "200k")
      (footprint "0603 RES")
      (description "(0603SAF2003T5E) Res Thick Film 0603 200K Ohm 1% 0.1W(1/10W) ±100ppm/°C Pad SMD T/R")
      (fields
        (field (name "MANUFACTURER") "Royal Electronic Factory")
        (field (name "MANUFACTURER PART NUMBER") "0603SAF2003T5E")
        (field (name "DESIGNED BY") "Eren/Mehmet")
      )
      (libsource (lib "Passive") (part "RES 200kOhm %1 SMD 0603"))
    )
    (comp (ref "R7")
      (value "10k")
      (footprint "0603 RES")
      (description "100mW Thick Film Resistors ±100ppm/℃ ±1% 10kΩ 0603 Chip Resistor - Surface Mount ROHS")
      (fields
        (field (name "MANUFACTURER") "Yageo Group")
        (field (name "MANUFACTURER PART NUMBER") "RC0603FR-0710KL")
      )
      (libsource (lib "Passive") (part "RES 10kOhm %1 SMD 0603"))
    )
    (comp (ref "R8")
      (value "330R")
      (footprint "0603 RES")
      (description "100Mw Thick Film Resistors 100Ppm/ 1% 330 0603 Chip Resistor Surface Mount Rohs")
      (fields
        (field (name "MANUFACTURER") "Yageo Group")
        (field (name "MANUFACTURER PART NUMBER") "RC0603FR-07330RL")
        (field (name "DESIGNED BY") "Eren")
      )
      (libsource (lib "Passive") (part "RES 330Ohm %1 SMD 0603"))
    )
    (comp (ref "R9")
      (value "10k")
      (footprint "0603 RES")
      (description "100mW Thick Film Resistors ±100ppm/℃ ±1% 10kΩ 0603 Chip Resistor - Surface Mount ROHS")
      (fields
        (field (name "MANUFACTURER") "Yageo Group")
        (field (name "MANUFACTURER PART NUMBER") "RC0603FR-0710KL")
      )
      (libsource (lib "Passive") (part "RES 10kOhm %1 SMD 0603"))
    )
    (comp (ref "R10")
      (value "3.3k")
      (footprint "0603 RES")
      (description "Res Thick Film 0603 3.3K Ohm 5% 0.1W(1/10W) ±100ppm/C Pad SMD T/R")
      (fields
        (field (name "MANUFACTURER") "Royal Ohm")
        (field (name "MANUFACTURER PART NUMBER") "0603SAJ0332T5E")
      )
      (libsource (lib "Passive") (part "RES 3.3kOhm %5 SMD 0603"))
    )
    (comp (ref "R11")
      (value "330R")
      (footprint "0603 RES")
      (description "100Mw Thick Film Resistors 100Ppm/ 1% 330 0603 Chip Resistor Surface Mount Rohs")
      (fields
        (field (name "MANUFACTURER") "Yageo Group")
        (field (name "MANUFACTURER PART NUMBER") "RC0603FR-07330RL")
        (field (name "DESIGNED BY") "Eren")
      )
      (libsource (lib "Passive") (part "RES 330Ohm %1 SMD 0603"))
    )
    (comp (ref "R12")
      (value "1k ohm")
      (footprint "0603 RES")
      (fields
        (field (name "MANUFACTURER") "Yageo")
        (field (name "MANUFACTURER PART NUMBER") "RC0603JR-071KL")
        (field (name "TOLERANCE") "5%")
        (field (name "DESIGNED BY") "Eren/Mehmet")
      )
      (libsource (lib "Passive") (part "RES 1kOhm %5 SMD 0603"))
    )
    (comp (ref "R13")
      (value "10k")
      (footprint "0603 RES")
      (fields
        (field (name "MANUFACTURER") "Yageo")
        (field (name "MANUFACTURER PART NUMBER") "RC0603JR-0710KL")
        (field (name "TOLERANCE") "5%")
        (field (name "DESIGNED BY") "Eren/Mehmet")
      )
      (libsource (lib "Passive") (part "RES 10kOhm %5 SMD 0603"))
    )
    (comp (ref "R14")
      (value "4.7k")
      (footprint "0603 RES")
      (description "Res Thick Film 1.6 x 0.8 mm 4.7K Ohm 1% 0.1W(1/10W) 100ppm/ C Molded SMD Paper T/R")
      (fields
        (field (name "MANUFACTURER") "Yageo Group")
        (field (name "MANUFACTURER PART NUMBER") "RC0603FR-074K7L")
      )
      (libsource (lib "Passive") (part "RES 4.7k Ohm %1 SMD 0603"))
    )
    (comp (ref "R15")
      (value "470R")
      (footprint "0603 RES")
      (description "RES.(1608) 0603 470 Ohms 1% 1/10W AUTOMOTIV")
      (fields
        (field (name "MANUFACTURER") "Royal Ohm")
        (field (name "MANUFACTURER PART NUMBER") "CQ03SAF4700T5E")
      )
      (libsource (lib "Passive") (part "RES  470 Ohm %1 SMD 0603"))
    )
    (comp (ref "R16")
      (value "47k")
      (footprint "0603 RES")
      (description "RES.(1608) 0603 47K Ohms 5% 1/10W-S 100PPM")
      (fields
        (field (name "MANUFACTURER") "Royal Ohm")
        (field (name "MANUFACTURER PART NUMBER") "0603SAJ0473TDE")
      )
      (libsource (lib "Passive") (part "RES 47k Ohm %5 SMD 0603"))
    )
    (comp (ref "R17")
      (value "1k ohm")
      (footprint "0603 RES")
      (fields
        (field (name "MANUFACTURER") "Yageo")
        (field (name "MANUFACTURER PART NUMBER") "RC0603JR-071KL")
        (field (name "TOLERANCE") "5%")
        (field (name "DESIGNED BY") "Eren/Mehmet")
      )
      (libsource (lib "Passive") (part "RES 1kOhm %5 SMD 0603"))
    )
    (comp (ref "R18")
      (value "330R")
      (footprint "0603 RES")
      (description "100Mw Thick Film Resistors 100Ppm/ 1% 330 0603 Chip Resistor Surface Mount Rohs")
      (fields
        (field (name "MANUFACTURER") "Yageo Group")
        (field (name "MANUFACTURER PART NUMBER") "RC0603FR-07330RL")
        (field (name "DESIGNED BY") "Eren")
      )
      (libsource (lib "Passive") (part "RES 330Ohm %1 SMD 0603"))
    )
    (comp (ref "R19")
      (value "3.3k")
      (footprint "0603 RES")
      (description "Res Thick Film 0603 3.3K Ohm 5% 0.1W(1/10W) ±100ppm/C Pad SMD T/R")
      (fields
        (field (name "MANUFACTURER") "Royal Ohm")
        (field (name "MANUFACTURER PART NUMBER") "0603SAJ0332T5E")
      )
      (libsource (lib "Passive") (part "RES 3.3kOhm %5 SMD 0603"))
    )
    (comp (ref "R20")
      (value "330R")
      (footprint "0603 RES")
      (description "100Mw Thick Film Resistors 100Ppm/ 1% 330 0603 Chip Resistor Surface Mount Rohs")
      (fields
        (field (name "MANUFACTURER") "Yageo Group")
        (field (name "MANUFACTURER PART NUMBER") "RC0603FR-07330RL")
        (field (name "DESIGNED BY") "Eren")
      )
      (libsource (lib "Passive") (part "RES 330Ohm %1 SMD 0603"))
    )
    (comp (ref "R21")
      (value "10k")
      (footprint "0603 RES")
      (description "100mW Thick Film Resistors ±100ppm/℃ ±1% 10kΩ 0603 Chip Resistor - Surface Mount ROHS")
      (fields
        (field (name "MANUFACTURER") "Yageo Group")
        (field (name "MANUFACTURER PART NUMBER") "RC0603FR-0710KL")
      )
      (libsource (lib "Passive") (part "RES 10kOhm %1 SMD 0603"))
    )
    (comp (ref "R22")
      (value "10k")
      (footprint "0603 RES")
      (fields
        (field (name "MANUFACTURER") "Yageo")
        (field (name "MANUFACTURER PART NUMBER") "RC0603JR-0710KL")
        (field (name "TOLERANCE") "5%")
        (field (name "DESIGNED BY") "Eren/Mehmet")
      )
      (libsource (lib "Passive") (part "RES 10kOhm %5 SMD 0603"))
    )
    (comp (ref "R23")
      (value "470R")
      (footprint "0603 RES")
      (description "RES.(1608) 0603 470 Ohms 1% 1/10W AUTOMOTIV")
      (fields
        (field (name "MANUFACTURER") "Royal Ohm")
        (field (name "MANUFACTURER PART NUMBER") "CQ03SAF4700T5E")
      )
      (libsource (lib "Passive") (part "RES  470 Ohm %1 SMD 0603"))
    )
    (comp (ref "R24")
      (value "1k ohm")
      (footprint "0603 RES")
      (fields
        (field (name "MANUFACTURER") "Yageo")
        (field (name "MANUFACTURER PART NUMBER") "RC0603JR-071KL")
        (field (name "TOLERANCE") "5%")
        (field (name "DESIGNED BY") "Eren/Mehmet")
      )
      (libsource (lib "Passive") (part "RES 1kOhm %5 SMD 0603"))
    )
    (comp (ref "R25")
      (value "5.1k")
      (footprint "0603 RES")
      (description "RES.(1608) 0603 5.1K Ohms 1% 1/10W-S 100PPM")
      (fields
        (field (name "MANUFACTURER") "Royal Ohm")
        (field (name "MANUFACTURER PART NUMBER") "0603SAF5101T5E")
      )
      (libsource (lib "Passive") (part "RES 5.1kOhm %1 SMD 0603"))
    )
    (comp (ref "R26")
      (value "5.1k")
      (footprint "0603 RES")
      (description "RES.(1608) 0603 5.1K Ohms 1% 1/10W-S 100PPM")
      (fields
        (field (name "MANUFACTURER") "Royal Ohm")
        (field (name "MANUFACTURER PART NUMBER") "0603SAF5101T5E")
      )
      (libsource (lib "Passive") (part "RES 5.1kOhm %1 SMD 0603"))
    )
    (comp (ref "R27")
      (value "1k ohm")
      (footprint "0603 RES")
      (fields
        (field (name "MANUFACTURER") "Yageo")
        (field (name "MANUFACTURER PART NUMBER") "RC0603JR-071KL")
        (field (name "TOLERANCE") "5%")
        (field (name "DESIGNED BY") "Eren/Mehmet")
      )
      (libsource (lib "Passive") (part "RES 1kOhm %5 SMD 0603"))
    )
    (comp (ref "R28")
      (value "OR")
      (footprint "0603 RES")
      (description "RES.(1608) 0603 0 Ohms 1% 1/10W")
      (fields (field (name "MANUFACTURER") "VIKING") (field (name "MANUFACTURER PART NUMBER") "CRT03F7-R0R0"))
      (libsource (lib "Passive") (part "RES 0R Ohms %1 SMD 0603"))
    )
    (comp (ref "R29")
      (value "OR")
      (footprint "0603 RES")
      (description "RES.(1608) 0603 0 Ohms 1% 1/10W")
      (fields (field (name "MANUFACTURER") "VIKING") (field (name "MANUFACTURER PART NUMBER") "CRT03F7-R0R0"))
      (libsource (lib "Passive") (part "RES 0R Ohms %1 SMD 0603"))
    )
    (comp (ref "R30")
      (value "1R")
      (footprint "0603 RES")
      (description "RES.(1608) 0603 1 Ohms 1% 1/10W AUTOMOTIV")
      (fields
        (field (name "MANUFACTURER") "Royal Ohm")
        (field (name "MANUFACTURER PART NUMBER") "CQ03SAF100KT5E")
      )
      (libsource (lib "Passive") (part "RES 1R Ohm %1 SMD 0603"))
    )
    (comp (ref "R31")
      (value "10k")
      (footprint "0603 RES")
      (description "100mW Thick Film Resistors ±100ppm/℃ ±1% 10kΩ 0603 Chip Resistor - Surface Mount ROHS")
      (fields
        (field (name "MANUFACTURER") "Yageo Group")
        (field (name "MANUFACTURER PART NUMBER") "RC0603FR-0710KL")
      )
      (libsource (lib "Passive") (part "RES 10kOhm %1 SMD 0603"))
    )
    (comp (ref "R32")
      (value "4.7k")
      (footprint "0603 RES")
      (description "Res Thick Film 1.6 x 0.8 mm 4.7K Ohm 1% 0.1W(1/10W) 100ppm/ C Molded SMD Paper T/R")
      (fields
        (field (name "MANUFACTURER") "Yageo Group")
        (field (name "MANUFACTURER PART NUMBER") "RC0603FR-074K7L")
      )
      (libsource (lib "Passive") (part "RES 4.7k Ohm %1 SMD 0603"))
    )
    (comp (ref "R33")
      (value "4.7k")
      (footprint "0603 RES")
      (description "Res Thick Film 1.6 x 0.8 mm 4.7K Ohm 1% 0.1W(1/10W) 100ppm/ C Molded SMD Paper T/R")
      (fields
        (field (name "MANUFACTURER") "Yageo Group")
        (field (name "MANUFACTURER PART NUMBER") "RC0603FR-074K7L")
      )
      (libsource (lib "Passive") (part "RES 4.7k Ohm %1 SMD 0603"))
    )
    (comp (ref "R34")
      (value "2.2k")
      (footprint "0603 RES")
      (description "Res Thick Film 0603 2.2K Ohm 1% 0.1W(1/10W) +/-100ppm/C Epoxy Pad SMD T/R")
      (fields
        (field (name "MANUFACTURER") "Yageo Group")
        (field (name "MANUFACTURER PART NUMBER") "RC0603FR-072K2L")
      )
      (libsource (lib "Passive") (part "RES 2.2k Ohm %1 SMD 0603"))
    )
    (comp (ref "R35")
      (value "2.2k")
      (footprint "0603 RES")
      (description "Res Thick Film 0603 2.2K Ohm 1% 0.1W(1/10W) +/-100ppm/C Epoxy Pad SMD T/R")
      (fields
        (field (name "MANUFACTURER") "Yageo Group")
        (field (name "MANUFACTURER PART NUMBER") "RC0603FR-072K2L")
      )
      (libsource (lib "Passive") (part "RES 2.2k Ohm %1 SMD 0603"))
    )
    (comp (ref "R36")
      (value "10k")
      (footprint "0603 RES")
      (description "100mW Thick Film Resistors ±100ppm/℃ ±1% 10kΩ 0603 Chip Resistor - Surface Mount ROHS")
      (fields
        (field (name "MANUFACTURER") "Yageo Group")
        (field (name "MANUFACTURER PART NUMBER") "RC0603FR-0710KL")
      )
      (libsource (lib "Passive") (part "RES 10kOhm %1 SMD 0603"))
    )
    (comp (ref "R37")
      (value "10k")
      (footprint "0603 RES")
      (description "100mW Thick Film Resistors ±100ppm/℃ ±1% 10kΩ 0603 Chip Resistor - Surface Mount ROHS")
      (fields
        (field (name "MANUFACTURER") "Yageo Group")
        (field (name "MANUFACTURER PART NUMBER") "RC0603FR-0710KL")
      )
      (libsource (lib "Passive") (part "RES 10kOhm %1 SMD 0603"))
    )
    (comp (ref "R38")
      (value "10k")
      (footprint "0603 RES")
      (description "100mW Thick Film Resistors ±100ppm/℃ ±1% 10kΩ 0603 Chip Resistor - Surface Mount ROHS")
      (fields
        (field (name "MANUFACTURER") "Yageo Group")
        (field (name "MANUFACTURER PART NUMBER") "RC0603FR-0710KL")
      )
      (libsource (lib "Passive") (part "RES 10kOhm %1 SMD 0603"))
    )
    (comp (ref "R39")
      (value "1R")
      (footprint "0603 RES")
      (description "RES.(1608) 0603 1 Ohms 1% 1/10W AUTOMOTIV")
      (fields
        (field (name "MANUFACTURER") "Royal Ohm")
        (field (name "MANUFACTURER PART NUMBER") "CQ03SAF100KT5E")
      )
      (libsource (lib "Passive") (part "RES 1R Ohm %1 SMD 0603"))
    )
    (comp (ref "R40")
      (value "1R")
      (footprint "0603 RES")
      (description "RES.(1608) 0603 1 Ohms 1% 1/10W AUTOMOTIV")
      (fields
        (field (name "MANUFACTURER") "Royal Ohm")
        (field (name "MANUFACTURER PART NUMBER") "CQ03SAF100KT5E")
      )
      (libsource (lib "Passive") (part "RES 1R Ohm %1 SMD 0603"))
    )
    (comp (ref "R41")
      (value "1R")
      (footprint "0603 RES")
      (description "RES.(1608) 0603 1 Ohms 1% 1/10W AUTOMOTIV")
      (fields
        (field (name "MANUFACTURER") "Royal Ohm")
        (field (name "MANUFACTURER PART NUMBER") "CQ03SAF100KT5E")
      )
      (libsource (lib "Passive") (part "RES 1R Ohm %1 SMD 0603"))
    )
    (comp (ref "R42")
      (value "10k")
      (footprint "0603 RES")
      (description "100mW Thick Film Resistors ±100ppm/℃ ±1% 10kΩ 0603 Chip Resistor - Surface Mount ROHS")
      (fields
        (field (name "MANUFACTURER") "Yageo Group")
        (field (name "MANUFACTURER PART NUMBER") "RC0603FR-0710KL")
      )
      (libsource (lib "Passive") (part "RES 10kOhm %1 SMD 0603"))
    )
    (comp (ref "SW1")
      (value "SWITCH TACT 3.65x6.10 2.50mm 180gF SMT V/T")
      (footprint "L-KLS7-TS3611-2.5-180-T")
      (fields (field (name "PART NUMBER") "L-KLS7-TS3611-2.5-180-T"))
      (libsource (lib "Electromechanical") (part "L-KLS7-TS3611-2.5-180-T"))
    )
    (comp (ref "SW2")
      (value "SWITCH TACT 3.65x6.10 2.50mm 180gF SMT V/T")
      (footprint "L-KLS7-TS3611-2.5-180-T")
      (fields (field (name "PART NUMBER") "L-KLS7-TS3611-2.5-180-T"))
      (libsource (lib "Electromechanical") (part "L-KLS7-TS3611-2.5-180-T"))
    )
    (comp (ref "U1")
      (value "Buck Switching Regulator IC Positive Adjustable 0.8V 1 Output 5A 8-SOIC (0.154\", 3.90mm Width) Exposed Pad")
      (footprint "SO-8EP")
      (fields
        (field (name "MANUFACTURER") "Diodes Inc.")
        (field (name "MANUFACTURER PART NUMBER") "AP64500SP-13")
      )
      (libsource (lib "Integrated Circuits - IC") (part "AP64500SP-13"))
    )
    (comp (ref "U2")
      (value "L86-M33")
      (footprint "L86-M33")
      (description "GLONASS/GPS/QZSS Module 18, 4x18, 4x6, 4mm SMD w/Antenna L86-M33")
      (fields
        (field (name "MANUFACTURER") "Quectel Wireless Solutions")
        (field (name "DESIGNED BY") "Eren/Mehmet")
      )
      (libsource (lib "Sensors & Modules") (part "L86-M33"))
    )
    (comp (ref "U3")
      (value "IC-816 OPTOISO SMD4 LITEON")
      (footprint "SMD4")
      (description "Transistor Output Optocoupler, 1-Element, 5000V Isolation")
      (fields
        (field (name "MANUFACTURER") "Lite-On")
        (field (name "MANUFACTURER PART NUMBER") "LTV-816S-TA1-C")
      )
      (libsource (lib "Integrated Circuits - IC") (part "LTV-816S-TA1-C"))
    )
    (comp (ref "U4")
      (value "IC-816 OPTOISO SMD4 LITEON")
      (footprint "SMD4")
      (description "Transistor Output Optocoupler, 1-Element, 5000V Isolation")
      (fields
        (field (name "MANUFACTURER") "Lite-On")
        (field (name "MANUFACTURER PART NUMBER") "LTV-816S-TA1-C")
      )
      (libsource (lib "Integrated Circuits - IC") (part "LTV-816S-TA1-C"))
    )
    (comp (ref "U5")
      (value "IMU ACCEL/GYRO/MAG I2C/SPI 24QFN")
      (footprint "TFQFN-24")
      (description "Accelerometer, Gyroscope, Magnetometer, 9 Axis Sensor I2C, SPI Output")
      (libsource (lib "Sensors & Modules") (part "MPU9250"))
    )
    (comp (ref "U6")
      (value "Bluetooth, WiFi 802.11b/g/n, Bluetooth v5.0 Transceiver Module 2.4GHz Antenna Not Included, U.FL Surface Mount")
      (footprint "ESP32-S3_WROOM-1U")
      (fields
        (field (name "MANUFACTURER") "Espressif Systems")
        (field (name "MANUFACTURER PART NUMBER") "ESP32-S3-WROOM-1U-N16R8")
      )
      (libsource (lib "Integrated Circuits - IC") (part "ESP32-S3-WROOM-1U-N16R8"))
    )
    (comp (ref "U7")
      (value "DIODE TVS 5.25VWM 17VC SOT23-6")
      (footprint "SOT23-6L")
      (description "STMicroelectronics USBLC6-2SC6 TVS diode surge protection on full tape reel")
      (fields
        (field (name "MANUFACTURER") "STMicroelectronics")
        (field (name "MANUFACTURER PART NUMBER") "USBLC6-2SC6")
      )
      (libsource (lib "Integrated Circuits - IC") (part "USBLC6-2SC6"))
    )
    (comp (ref "U8")
      (value "MS5611-01BA03")
      (footprint "MS5611-01BA03")
      (description "Pressure Sensor 1.44V to 3.6V 0.01bar to 1.2bar Absolute 8-Pin QFN T/R")
      (fields
        (field (name "MANUFACTURER") "TE Connectivity")
        (field (name "MANUFACTURER PART NUMBER") "MS561101BA03-50")
        (field (name "DESIGNED BY") "Eren/Mehmet")
      )
      (libsource (lib "Sensors & Modules") (part "MS5611"))
    )
    (comp (ref "U9")
      (value "Accelerometer X, Y, Z Axis ±200g 0.05Hz ~ 1.6kHz 14-LGA (3x5)")
      (footprint "LGA-14")
      (description "3-Axis, ±200 g Digital MEMS Accelerometer")
      (fields
        (field (name "MANUFACTURER") "Analog Devices")
        (field (name "MANUFACTURER PART NUMBER") "ADXL375BCCZ-RL7")
      )
      (libsource (lib "Sensors & Modules") (part "ADXL375"))
    )
    (comp (ref "U10")
      (value "IC-3232 DRVR/RCVR MLTCH RS232 16TSSOP")
      (footprint "TSSOP-16")
      (description "IC, Transceiver, RS232 (2)Transmitters/(2)Receivers, 250Kbit, TSSOP-16, -40C to +85C")
      (fields
        (field (name "MANUFACTURER") "Texas Instruments")
        (field (name "MANUFACTURER PART NUMBER") "MAX3232IPWR")
      )
      (libsource (lib "Integrated Circuits - IC") (part "MAX3232IPWR"))
    )
    (comp (ref "U11")
      (value "EBYTE Sx1262 E22-900M30S")
      (footprint "E22 900M30S")
      (description "EBYTE Sx1262 E22-900M30S 850 - 930 MHZ 30Dbm Lora Modül 12Km")
      (libsource (lib "Sensors & Modules") (part "E22-900M30S"))
    )
  )
  (nets
    (net (code "1") (name "/1PPS") (class "Default")
      (node (ref "R17") (pin "1") (pintype "passive"))
      (node (ref "U2") (pin "6") (pinfunction "1PPS_6") (pintype "passive"))
    )
    (net (code "2") (name "/BOOT") (class "Default")
      (node (ref "C22") (pin "1") (pintype "passive"))
      (node (ref "R7") (pin "2") (pintype "passive"))
      (node (ref "SW2") (pin "1") (pinfunction "1_1") (pintype "passive"))
      (node (ref "U6") (pin "27") (pinfunction "IO0_27") (pintype "passive"))
    )
    (net (code "3") (name "/BUZZER") (class "Default")
      (node (ref "R24") (pin "1") (pintype "passive"))
      (node (ref "U6") (pin "9") (pinfunction "IO16_9") (pintype "passive"))
    )
    (net (code "4") (name "/D+") (class "Default")
      (node (ref "R29") (pin "2") (pintype "passive"))
      (node (ref "U6") (pin "14") (pinfunction "IO20_14") (pintype "passive"))
    )
    (net (code "5") (name "/D-") (class "Default")
      (node (ref "R28") (pin "2") (pintype "passive"))
      (node (ref "U6") (pin "13") (pinfunction "IO19_13") (pintype "passive"))
    )
    (net (code "6") (name "/EN") (class "Default")
      (node (ref "C15") (pin "1") (pintype "passive"))
      (node (ref "R21") (pin "1") (pintype "passive"))
      (node (ref "SW1") (pin "1") (pinfunction "1_1") (pintype "passive"))
      (node (ref "U6") (pin "3") (pinfunction "EN_3") (pintype "passive"))
    )
    (net (code "7") (name "/GPS_RST") (class "Default")
      (node (ref "R14") (pin "1") (pintype "passive"))
      (node (ref "U6") (pin "11") (pinfunction "IO18_11") (pintype "passive"))
    )
    (net (code "8") (name "/GPS_RX") (class "Default")
      (node (ref "U2") (pin "1") (pinfunction "RXD1_1") (pintype "passive"))
      (node (ref "U6") (pin "32") (pinfunction "IO39_32") (pintype "passive"))
    )
    (net (code "9") (name "/GPS_TX") (class "Default")
      (node (ref "U2") (pin "2") (pinfunction "TXD1_2") (pintype "passive"))
      (node (ref "U6") (pin "31") (pinfunction "IO38_31") (pintype "passive"))
    )
    (net (code "10") (name "/I2C0_SCL") (class "Default")
      (node (ref "R35") (pin "1") (pintype "passive"))
      (node (ref "U5") (pin "23") (pinfunction "SCL/SCLK_23") (pintype "passive"))
      (node (ref "U6") (pin "39") (pinfunction "IO1_39") (pintype "passive"))
    )
    (net (code "11") (name "/I2C0_SDA") (class "Default")
      (node (ref "R34") (pin "1") (pintype "passive"))
      (node (ref "U5") (pin "24") (pinfunction "SDA/SDI_24") (pintype "passive"))
      (node (ref "U6") (pin "38") (pinfunction "IO2_38") (pintype "passive"))
    )
    (net (code "12") (name "/I2C1_SCL") (class "Default")
      (node (ref "R33") (pin "1") (pintype "passive"))
      (node (ref "U6") (pin "34") (pinfunction "IO41_34") (pintype "passive"))
      (node (ref "U8") (pin "8") (pinfunction "SCLK_8") (pintype "passive"))
      (node (ref "U9") (pin "14") (pinfunction "SCL/SCLK_14") (pintype "passive"))
    )
    (net (code "13") (name "/I2C1_SDA") (class "Default")
      (node (ref "R32") (pin "1") (pintype "passive"))
      (node (ref "U6") (pin "35") (pinfunction "IO42_35") (pintype "passive"))
      (node (ref "U8") (pin "7") (pinfunction "SDI/SDA_7") (pintype "passive"))
      (node (ref "U9") (pin "13") (pinfunction "SDA/SDI/SDIO_13") (pintype "passive"))
    )
    (net (code "14") (name "/MISO") (class "Default")
      (node (ref "U11") (pin "16") (pinfunction "MISO_16") (pintype "passive"))
      (node (ref "U6") (pin "20") (pinfunction "IO12_20") (pintype "passive"))
    )
    (net (code "15") (name "/MOSI") (class "Default")
      (node (ref "U11") (pin "17") (pinfunction "MOSI_17") (pintype "passive"))
      (node (ref "U6") (pin "19") (pinfunction "IO11_19") (pintype "passive"))
    )
    (net (code "16") (name "/PYRO_DROGUE") (class "Default")
      (node (ref "R15") (pin "1") (pintype "passive"))
      (node (ref "R37") (pin "1") (pintype "passive"))
      (node (ref "R8") (pin "2") (pintype "passive"))
      (node (ref "U6") (pin "5") (pinfunction "IO5_5") (pintype "passive"))
    )
    (net (code "17") (name "/PYRO_DROGUE_-") (class "Default")
      (node (ref "D4") (pin "A") (pinfunction "1_A") (pintype "passive"))
      (node (ref "J4") (pin "2") (pinfunction "2_2") (pintype "passive"))
      (node (ref "Q1") (pin "D") (pintype "passive"))
      (node (ref "R10") (pin "2") (pintype "passive"))
    )
    (net (code "18") (name "/PYRO_MAIN") (class "Default")
      (node (ref "R18") (pin "2") (pintype "passive"))
      (node (ref "R23") (pin "1") (pintype "passive"))
      (node (ref "R38") (pin "1") (pintype "passive"))
      (node (ref "U6") (pin "6") (pinfunction "IO6_6") (pintype "passive"))
    )
    (net (code "19") (name "/PYRO_MAİN_-") (class "Default")
      (node (ref "D10") (pin "A") (pinfunction "1_A") (pintype "passive"))
      (node (ref "J1") (pin "2") (pinfunction "2_2") (pintype "passive"))
      (node (ref "Q4") (pin "D") (pintype "passive"))
      (node (ref "R19") (pin "2") (pintype "passive"))
    )
    (net (code "20") (name "/RESET_N") (class "Default")
      (node (ref "Q2") (pin "3") (pinfunction "C_3") (pintype "passive"))
      (node (ref "U2") (pin "10") (pinfunction "RESET_10") (pintype "passive"))
    )
    (net (code "21") (name "/RF_BUSY") (class "Default")
      (node (ref "U11") (pin "14") (pinfunction "BUSY_14") (pintype "passive"))
      (node (ref "U6") (pin "22") (pinfunction "IO14_22") (pintype "passive"))
    )
    (net (code "22") (name "/RF_CS") (class "Default")
      (node (ref "R42") (pin "1") (pintype "passive"))
      (node (ref "U11") (pin "19") (pinfunction "NSS_19") (pintype "passive"))
      (node (ref "U6") (pin "17") (pinfunction "IO9_17") (pintype "passive"))
    )
    (net (code "23") (name "/RF_DIO1") (class "Default")
      (node (ref "U11") (pin "13") (pinfunction "DIO1_13") (pintype "passive"))
      (node (ref "U6") (pin "23") (pinfunction "IO21_23") (pintype "passive"))
    )
    (net (code "24") (name "/RF_NRST") (class "Default")
      (node (ref "R31") (pin "2") (pintype "passive"))
      (node (ref "U11") (pin "15") (pinfunction "NRST_15") (pintype "passive"))
      (node (ref "U6") (pin "21") (pinfunction "IO13_21") (pintype "passive"))
    )
    (net (code "25") (name "/RF_RXEN") (class "Default")
      (node (ref "U11") (pin "7") (pinfunction "TXEN_7") (pintype "passive"))
      (node (ref "U6") (pin "24") (pinfunction "IO47_24") (pintype "passive"))
    )
    (net (code "26") (name "/RF_TXEN") (class "Default")
      (node (ref "U11") (pin "6") (pinfunction "RXEN_6") (pintype "passive"))
      (node (ref "U6") (pin "25") (pinfunction "IO48_25") (pintype "passive"))
    )
    (net (code "27") (name "/RS232_RX") (class "Default")
      (node (ref "J6") (pin "3") (pinfunction "RxD_3") (pintype "passive"))
      (node (ref "U10") (pin "13") (pinfunction "RIN1_13") (pintype "passive"))
    )
    (net (code "28") (name "/RS232_TX") (class "Default")
      (node (ref "J6") (pin "2") (pinfunction "TxD_2") (pintype "passive"))
      (node (ref "U10") (pin "14") (pinfunction "DOUT1_14") (pintype "passive"))
    )
    (net (code "29") (name "/SPI_SCK") (class "Default")
      (node (ref "U11") (pin "18") (pinfunction "SCK_18") (pintype "passive"))
      (node (ref "U6") (pin "18") (pinfunction "IO10_18") (pintype "passive"))
    )
    (net (code "30") (name "/STATUS_LED") (class "Default")
      (node (ref "R27") (pin "2") (pintype "passive"))
      (node (ref "U6") (pin "10") (pinfunction "IO17_10") (pintype "passive"))
    )
    (net (code "31") (name "/TTL_RX") (class "Default")
      (node (ref "U10") (pin "12") (pinfunction "ROUT1_12") (pintype "passive"))
      (node (ref "U6") (pin "36") (pinfunction "RXD0_36") (pintype "passive"))
    )
    (net (code "32") (name "/TTL_TX") (class "Default")
      (node (ref "U10") (pin "11") (pinfunction "DIN1_11") (pintype "passive"))
      (node (ref "U6") (pin "37") (pinfunction "TXD0_37") (pintype "passive"))
    )
    (net (code "33") (name "/USB_D+") (class "Default")
      (node (ref "J5") (pin "A6") (pinfunction "DP1_A6") (pintype "passive"))
      (node (ref "J5") (pin "B6") (pinfunction "DP2_B6") (pintype "passive"))
      (node (ref "U7") (pin "3") (pinfunction "IO2_3") (pintype "passive"))
    )
    (net (code "34") (name "/USB_D-") (class "Default")
      (node (ref "J5") (pin "A7") (pinfunction "DN1_A7") (pintype "passive"))
      (node (ref "J5") (pin "B7") (pinfunction "DN2_B7") (pintype "passive"))
      (node (ref "U7") (pin "1") (pinfunction "IO1_1") (pintype "passive"))
    )
    (net (code "35") (name "/V_BCKP") (class "Default")
      (node (ref "C1") (pin "2") (pintype "passive"))
      (node (ref "C34") (pin "2") (pintype "passive"))
      (node (ref "D1") (pin "3") (pinfunction "3_3") (pintype "passive"))
      (node (ref "U2") (pin "5") (pinfunction "V_BCKP_5") (pintype "passive"))
    )
    (net (code "36") (name "3V3") (class "Default")
      (node (ref "C10") (pin "2") (pintype "passive"))
      (node (ref "C13") (pin "1") (pintype "passive"))
      (node (ref "C14") (pin "1") (pintype "passive"))
      (node (ref "C28") (pin "1") (pintype "passive"))
      (node (ref "C8") (pin "2") (pintype "passive"))
      (node (ref "C9") (pin "2") (pintype "passive"))
      (node (ref "D1") (pin "1") (pinfunction "1_1") (pintype "passive"))
      (node (ref "D13") (pin "K") (pinfunction "2_K") (pintype "passive"))
      (node (ref "FB1") (pin "1") (pinfunction "1_1") (pintype "passive"))
      (node (ref "FB3") (pin "2") (pinfunction "2_2") (pintype "passive"))
      (node (ref "FB4") (pin "1") (pinfunction "1_1") (pintype "passive"))
      (node (ref "FB5") (pin "1") (pinfunction "1_1") (pintype "passive"))
      (node (ref "FB6") (pin "1") (pinfunction "1_1") (pintype "passive"))
      (node (ref "L1") (pin "2") (pinfunction "2_2") (pintype "passive"))
      (node (ref "LS1") (pin "1") (pinfunction "(+)_1") (pintype "passive"))
      (node (ref "R1") (pin "2") (pintype "passive"))
      (node (ref "R12") (pin "2") (pintype "passive"))
      (node (ref "R2") (pin "2") (pintype "passive"))
      (node (ref "R21") (pin "2") (pintype "passive"))
      (node (ref "R31") (pin "1") (pintype "passive"))
      (node (ref "R32") (pin "2") (pintype "passive"))
      (node (ref "R33") (pin "2") (pintype "passive"))
      (node (ref "R34") (pin "2") (pintype "passive"))
      (node (ref "R35") (pin "2") (pintype "passive"))
      (node (ref "R36") (pin "1") (pintype "passive"))
      (node (ref "R42") (pin "2") (pintype "passive"))
      (node (ref "R7") (pin "1") (pintype "passive"))
      (node (ref "U10") (pin "16") (pinfunction "Vcc_16") (pintype "passive"))
      (node (ref "U6") (pin "2") (pinfunction "3V3_2") (pintype "passive"))
      (node (ref "U9") (pin "7") (pinfunction "CS_7") (pintype "passive"))
    )
    (net (code "37") (name "GND") (class "Default")
      (node (ref "BT1") (pin "2") (pinfunction "2_2") (pintype "passive"))
      (node (ref "C1") (pin "1") (pintype "passive"))
      (node (ref "C10") (pin "1") (pintype "passive"))
      (node (ref "C11") (pin "1") (pintype "passive"))
      (node (ref "C12") (pin "1") (pintype "passive"))
      (node (ref "C13") (pin "2") (pintype "passive"))
      (node (ref "C14") (pin "2") (pintype "passive"))
      (node (ref "C15") (pin "2") (pintype "passive"))
      (node (ref "C16") (pin "2") (pintype "passive"))
      (node (ref "C18") (pin "2") (pintype "passive"))
      (node (ref "C19") (pin "2") (pintype "passive"))
      (node (ref "C20") (pin "1") (pintype "passive"))
      (node (ref "C21") (pin "1") (pintype "passive"))
      (node (ref "C22") (pin "2") (pintype "passive"))
      (node (ref "C23") (pin "1") (pintype "passive"))
      (node (ref "C25") (pin "2") (pintype "passive"))
      (node (ref "C27") (pin "2") (pintype "passive"))
      (node (ref "C28") (pin "2") (pintype "passive"))
      (node (ref "C29") (pin "1") (pintype "passive"))
      (node (ref "C30") (pin "2") (pintype "passive"))
      (node (ref "C33") (pin "1") (pintype "passive"))
      (node (ref "C34") (pin "1") (pintype "passive"))
      (node (ref "C36") (pin "2") (pintype "passive"))
      (node (ref "C4") (pin "2") (pintype "passive"))
      (node (ref "C5") (pin "2") (pintype "passive"))
      (node (ref "C6") (pin "1") (pintype "passive"))
      (node (ref "C7") (pin "1") (pintype "passive"))
      (node (ref "C8") (pin "1") (pintype "passive"))
      (node (ref "C9") (pin "1") (pintype "passive"))
      (node (ref "D12") (pin "2") (pinfunction "2_2") (pintype "power_in"))
      (node (ref "D14") (pin "2") (pinfunction "2_2") (pintype "power_in"))
      (node (ref "D16") (pin "A") (pinfunction "1_A") (pintype "passive"))
      (node (ref "D3") (pin "2") (pinfunction "2_2") (pintype "power_in"))
      (node (ref "D8") (pin "2") (pinfunction "2_2") (pintype "power_in"))
      (node (ref "J2") (pin "2") (pinfunction "2_2") (pintype "passive"))
      (node (ref "J5") (pin "A1/B12") (pinfunction "GND_A1/B12") (pintype "passive"))
      (node (ref "J5") (pin "B1/A12") (pinfunction "GND_B1/A12") (pintype "passive"))
      (node (ref "J5") (pin "SHIELD") (pinfunction "SHIELD_SHIELD") (pintype "passive"))
      (node (ref "J6") (pin "5") (pinfunction "GND_5") (pintype "passive"))
      (node (ref "Q2") (pin "2") (pinfunction "E_2") (pintype "passive"))
      (node (ref "Q3") (pin "2") (pinfunction "E_2") (pintype "passive"))
      (node (ref "Q5") (pin "2") (pinfunction "E_2") (pintype "passive"))
      (node (ref "R16") (pin "1") (pintype "passive"))
      (node (ref "R25") (pin "1") (pintype "passive"))
      (node (ref "R26") (pin "2") (pintype "passive"))
      (node (ref "R3") (pin "2") (pintype "passive"))
      (node (ref "R30") (pin "2") (pintype "passive"))
      (node (ref "R37") (pin "2") (pintype "passive"))
      (node (ref "R38") (pin "2") (pintype "passive"))
      (node (ref "R39") (pin "2") (pintype "passive"))
      (node (ref "R4") (pin "1") (pintype "passive"))
      (node (ref "R40") (pin "2") (pintype "passive"))
      (node (ref "R41") (pin "2") (pintype "passive"))
      (node (ref "R6") (pin "1") (pintype "passive"))
      (node (ref "R9") (pin "2") (pintype "passive"))
      (node (ref "SW1") (pin "2") (pinfunction "2_2") (pintype "passive"))
      (node (ref "SW2") (pin "2") (pinfunction "2_2") (pintype "passive"))
      (node (ref "U1") (pin "7") (pinfunction "GND_7") (pintype "passive"))
      (node (ref "U1") (pin "9") (pinfunction "EXPOSED_PAD_9") (pintype "passive"))
      (node (ref "U10") (pin "15") (pinfunction "GND_15") (pintype "passive"))
      (node (ref "U11") (pin "1") (pinfunction "GND_1") (pintype "passive"))
      (node (ref "U11") (pin "11") (pinfunction "GND_11") (pintype "passive"))
      (node (ref "U11") (pin "12") (pinfunction "GND_12") (pintype "passive"))
      (node (ref "U11") (pin "2") (pinfunction "GND_2") (pintype "passive"))
      (node (ref "U11") (pin "20") (pinfunction "GND_20") (pintype "passive"))
      (node (ref "U11") (pin "22") (pinfunction "GND_22") (pintype "passive"))
      (node (ref "U11") (pin "3") (pinfunction "GND_3") (pintype "passive"))
      (node (ref "U11") (pin "4") (pinfunction "GND_4") (pintype "passive"))
      (node (ref "U11") (pin "5") (pinfunction "GND_5") (pintype "passive"))
      (node (ref "U2") (pin "12") (pinfunction "GND_12") (pintype "passive"))
      (node (ref "U2") (pin "3") (pinfunction "GND_3") (pintype "passive"))
      (node (ref "U3") (pin "2") (pinfunction "KATOT_2") (pintype "passive"))
      (node (ref "U4") (pin "2") (pinfunction "KATOT_2") (pintype "passive"))
      (node (ref "U5") (pin "11") (pinfunction "FSYNC_11") (pintype "passive"))
      (node (ref "U5") (pin "18") (pinfunction "GND_18") (pintype "passive"))
      (node (ref "U5") (pin "20") (pinfunction "RESV_20") (pintype "passive"))
      (node (ref "U5") (pin "25") (pinfunction "EXP_25") (pintype "passive"))
      (node (ref "U5") (pin "9") (pinfunction "AD0/SDO_9") (pintype "passive"))
      (node (ref "U6") (pin "1") (pinfunction "GND1_1") (pintype "passive"))
      (node (ref "U6") (pin "40") (pinfunction "GND2_40") (pintype "passive"))
      (node (ref "U6") (pin "41") (pinfunction "EPAD_41") (pintype "passive"))
      (node (ref "U7") (pin "2") (pinfunction "GND_2") (pintype "passive"))
      (node (ref "U8") (pin "3") (pinfunction "GND_3") (pintype "passive"))
      (node (ref "U8") (pin "4") (pinfunction "CSB_4") (pintype "passive"))
      (node (ref "U8") (pin "5") (pinfunction "CSB_5") (pintype "passive"))
      (node (ref "U9") (pin "11") (pinfunction "RESERVED_11") (pintype "passive"))
      (node (ref "U9") (pin "12") (pinfunction "SDO/ALTADDRESS_12") (pintype "passive"))
      (node (ref "U9") (pin "2") (pinfunction "GND_2") (pintype "passive"))
      (node (ref "U9") (pin "4") (pinfunction "GND_4") (pintype "passive"))
      (node (ref "U9") (pin "5") (pinfunction "GND_5") (pintype "passive"))
    )
    (net (code "38") (name "Net-(BT1-Pad1)") (class "Default")
      (node (ref "BT1") (pin "1") (pinfunction "1_1") (pintype "passive"))
      (node (ref "D1") (pin "2") (pinfunction "2_2") (pintype "passive"))
    )
    (net (code "39") (name "Net-(C3-Pad2)") (class "Default")
      (node (ref "C3") (pin "2") (pintype "passive"))
      (node (ref "R3") (pin "1") (pintype "passive"))
    )
    (net (code "40") (name "Net-(C12-Pad2)") (class "Default")
      (node (ref "C12") (pin "2") (pintype "passive"))
      (node (ref "R5") (pin "1") (pintype "passive"))
    )
    (net (code "41") (name "Net-(C17-Pad1)") (class "Default")
      (node (ref "C17") (pin "1") (pintype "passive"))
      (node (ref "R30") (pin "1") (pintype "passive"))
    )
    (net (code "42") (name "Net-(C24-Pad1)") (class "Default")
      (node (ref "C24") (pin "1") (pintype "passive"))
      (node (ref "C25") (pin "1") (pintype "passive"))
      (node (ref "C36") (pin "1") (pintype "passive"))
      (node (ref "FB6") (pin "2") (pinfunction "2_2") (pintype "passive"))
      (node (ref "U11") (pin "10") (pinfunction "VCC_10") (pintype "passive"))
      (node (ref "U11") (pin "9") (pinfunction "VCC_9") (pintype "passive"))
    )
    (net (code "43") (name "Net-(C24-Pad2)") (class "Default")
      (node (ref "C24") (pin "2") (pintype "passive"))
      (node (ref "R40") (pin "1") (pintype "passive"))
    )
    (net (code "44") (name "Net-(C26-Pad2)") (class "Default")
      (node (ref "C26") (pin "2") (pintype "passive"))
      (node (ref "R41") (pin "1") (pintype "passive"))
    )
    (net (code "45") (name "Net-(C35-Pad1)") (class "Default")
      (node (ref "C35") (pin "1") (pintype "passive"))
      (node (ref "R39") (pin "1") (pintype "passive"))
    )
    (net (code "46") (name "Net-(D3-Pad1)") (class "Default")
      (node (ref "D3") (pin "1") (pinfunction "1_1") (pintype "power_in"))
      (node (ref "R2") (pin "1") (pintype "passive"))
    )
    (net (code "47") (name "Net-(D5-Pad1)") (class "Default")
      (node (ref "D5") (pin "1") (pinfunction "1_1") (pintype "power_in"))
      (node (ref "R10") (pin "1") (pintype "passive"))
    )
    (net (code "48") (name "Net-(D6-Pad1)") (class "Default")
      (node (ref "D6") (pin "1") (pinfunction "1_1") (pintype "power_in"))
      (node (ref "R12") (pin "1") (pintype "passive"))
    )
    (net (code "49") (name "Net-(D8-Pad1)") (class "Default")
      (node (ref "D8") (pin "1") (pinfunction "1_1") (pintype "power_in"))
      (node (ref "R15") (pin "2") (pintype "passive"))
    )
    (net (code "50") (name "Net-(D9-1)") (class "Default")
      (node (ref "D9") (pin "A") (pinfunction "1_A") (pintype "passive"))
      (node (ref "FB2") (pin "2") (pinfunction "2_2") (pintype "passive"))
    )
    (net (code "51") (name "Net-(D11-Pad1)") (class "Default")
      (node (ref "D11") (pin "1") (pinfunction "1_1") (pintype "power_in"))
      (node (ref "R19") (pin "1") (pintype "passive"))
    )
    (net (code "52") (name "Net-(D12-Pad1)") (class "Default")
      (node (ref "D12") (pin "1") (pinfunction "1_1") (pintype "power_in"))
      (node (ref "R23") (pin "2") (pintype "passive"))
    )
    (net (code "53") (name "Net-(D13-1)") (class "Default")
      (node (ref "D13") (pin "A") (pinfunction "1_A") (pintype "passive"))
      (node (ref "LS1") (pin "2") (pinfunction "(-)_2") (pintype "passive"))
      (node (ref "Q5") (pin "3") (pinfunction "C_3") (pintype "passive"))
    )
    (net (code "54") (name "Net-(D14-Pad1)") (class "Default")
      (node (ref "D14") (pin "1") (pinfunction "1_1") (pintype "power_in"))
      (node (ref "R27") (pin "1") (pintype "passive"))
    )
    (net (code "55") (name "Net-(J5-CC1)") (class "Default")
      (node (ref "J5") (pin "A5") (pinfunction "CC1_A5") (pintype "passive"))
      (node (ref "R25") (pin "2") (pintype "passive"))
    )
    (net (code "56") (name "Net-(J5-CC2)") (class "Default")
      (node (ref "J5") (pin "B5") (pinfunction "CC2_B5") (pintype "passive"))
      (node (ref "R26") (pin "1") (pintype "passive"))
    )
    (net (code "57") (name "Net-(Q1-PadG)") (class "Default")
      (node (ref "Q1") (pin "G") (pintype "passive"))
      (node (ref "R11") (pin "1") (pintype "passive"))
      (node (ref "R13") (pin "2") (pintype "passive"))
    )
    (net (code "58") (name "Net-(Q2-B)") (class "Default")
      (node (ref "Q2") (pin "1") (pinfunction "B_1") (pintype "passive"))
      (node (ref "R14") (pin "2") (pintype "passive"))
      (node (ref "R16") (pin "2") (pintype "passive"))
    )
    (net (code "59") (name "Net-(Q3-B)") (class "Default")
      (node (ref "Q3") (pin "1") (pinfunction "B_1") (pintype "passive"))
      (node (ref "R17") (pin "2") (pintype "passive"))
    )
    (net (code "60") (name "Net-(Q3-C)") (class "Default")
      (node (ref "D6") (pin "2") (pinfunction "2_2") (pintype "power_in"))
      (node (ref "Q3") (pin "3") (pinfunction "C_3") (pintype "passive"))
    )
    (net (code "61") (name "Net-(Q4-PadG)") (class "Default")
      (node (ref "Q4") (pin "G") (pintype "passive"))
      (node (ref "R20") (pin "1") (pintype "passive"))
      (node (ref "R22") (pin "2") (pintype "passive"))
    )
    (net (code "62") (name "Net-(Q5-B)") (class "Default")
      (node (ref "Q5") (pin "1") (pinfunction "B_1") (pintype "passive"))
      (node (ref "R24") (pin "2") (pintype "passive"))
    )
    (net (code "63") (name "Net-(R28-Pad1)") (class "Default")
      (node (ref "R28") (pin "1") (pintype "passive"))
      (node (ref "U7") (pin "6") (pinfunction "IO1_6") (pintype "passive"))
    )
    (net (code "64") (name "Net-(R29-Pad1)") (class "Default")
      (node (ref "R29") (pin "1") (pintype "passive"))
      (node (ref "U7") (pin "4") (pinfunction "IO2_4") (pintype "passive"))
    )
    (net (code "65") (name "Net-(U1-BST)") (class "Default")
      (node (ref "C2") (pin "2") (pintype "passive"))
      (node (ref "U1") (pin "1") (pinfunction "BST_1") (pintype "passive"))
    )
    (net (code "66") (name "Net-(U1-COMP)") (class "Default")
      (node (ref "C11") (pin "2") (pintype "passive"))
      (node (ref "R5") (pin "2") (pintype "passive"))
      (node (ref "U1") (pin "6") (pinfunction "COMP_6") (pintype "passive"))
    )
    (net (code "67") (name "Net-(U1-FB)") (class "Default")
      (node (ref "R1") (pin "1") (pintype "passive"))
      (node (ref "R4") (pin "2") (pintype "passive"))
      (node (ref "U1") (pin "5") (pinfunction "FB_5") (pintype "passive"))
    )
    (net (code "68") (name "Net-(U1-RT{slash}CLK)") (class "Default")
      (node (ref "R6") (pin "2") (pintype "passive"))
      (node (ref "U1") (pin "4") (pinfunction "RT/CLK_4") (pintype "passive"))
    )
    (net (code "69") (name "Net-(U1-SW)") (class "Default")
      (node (ref "C2") (pin "1") (pintype "passive"))
      (node (ref "L1") (pin "1") (pinfunction "1_1") (pintype "passive"))
      (node (ref "U1") (pin "8") (pinfunction "SW_8") (pintype "passive"))
    )
    (net (code "70") (name "Net-(U2-VCC)") (class "Default")
      (node (ref "C3") (pin "1") (pintype "passive"))
      (node (ref "C4") (pin "1") (pintype "passive"))
      (node (ref "C5") (pin "1") (pintype "passive"))
      (node (ref "FB1") (pin "2") (pinfunction "2_2") (pintype "passive"))
      (node (ref "U2") (pin "4") (pinfunction "VCC_4") (pintype "passive"))
    )
    (net (code "71") (name "Net-(U3-ANOT)") (class "Default")
      (node (ref "R8") (pin "1") (pintype "passive"))
      (node (ref "U3") (pin "1") (pinfunction "ANOT_1") (pintype "passive"))
    )
    (net (code "72") (name "Net-(U3-EMİTER)") (class "Default")
      (node (ref "R11") (pin "2") (pintype "passive"))
      (node (ref "U3") (pin "3") (pinfunction "EMİTER_3") (pintype "passive"))
    )
    (net (code "73") (name "Net-(U4-ANOT)") (class "Default")
      (node (ref "R18") (pin "1") (pintype "passive"))
      (node (ref "U4") (pin "1") (pinfunction "ANOT_1") (pintype "passive"))
    )
    (net (code "74") (name "Net-(U4-EMİTER)") (class "Default")
      (node (ref "R20") (pin "2") (pintype "passive"))
      (node (ref "U4") (pin "3") (pinfunction "EMİTER_3") (pintype "passive"))
    )
    (net (code "75") (name "Net-(U5-REGOUT)") (class "Default")
      (node (ref "C19") (pin "1") (pintype "passive"))
      (node (ref "U5") (pin "10") (pinfunction "REGOUT_10") (pintype "passive"))
    )
    (net (code "76") (name "Net-(U5-VDD)") (class "Default")
      (node (ref "C16") (pin "1") (pintype "passive"))
      (node (ref "C17") (pin "2") (pintype "passive"))
      (node (ref "C18") (pin "1") (pintype "passive"))
      (node (ref "FB3") (pin "1") (pinfunction "1_1") (pintype "passive"))
      (node (ref "U5") (pin "1") (pinfunction "RESV_1") (pintype "passive"))
      (node (ref "U5") (pin "13") (pinfunction "VDD_13") (pintype "passive"))
      (node (ref "U5") (pin "22") (pinfunction "nCS_22") (pintype "passive"))
      (node (ref "U5") (pin "8") (pinfunction "VDDIO_8") (pintype "passive"))
    )
    (net (code "77") (name "Net-(U6-IO3)") (class "Default")
      (node (ref "R36") (pin "2") (pintype "passive"))
      (node (ref "U6") (pin "15") (pinfunction "IO3_15") (pintype "passive"))
    )
    (net (code "78") (name "Net-(U6-IO46)") (class "Default")
      (node (ref "R9") (pin "1") (pintype "passive"))
      (node (ref "U6") (pin "16") (pinfunction "IO46_16") (pintype "passive"))
    )
    (net (code "79") (name "Net-(U8-PS)") (class "Default")
      (node (ref "C23") (pin "2") (pintype "passive"))
      (node (ref "C35") (pin "2") (pintype "passive"))
      (node (ref "FB4") (pin "2") (pinfunction "2_2") (pintype "passive"))
      (node (ref "U8") (pin "1") (pinfunction "VDD_1") (pintype "passive"))
      (node (ref "U8") (pin "2") (pinfunction "PS_2") (pintype "passive"))
    )
    (net (code "80") (name "Net-(U9-VDDIO)") (class "Default")
      (node (ref "C26") (pin "1") (pintype "passive"))
      (node (ref "C27") (pin "1") (pintype "passive"))
      (node (ref "C29") (pin "2") (pintype "passive"))
      (node (ref "FB5") (pin "2") (pinfunction "2_2") (pintype "passive"))
      (node (ref "U9") (pin "1") (pinfunction "VDDIO_1") (pintype "passive"))
      (node (ref "U9") (pin "3") (pinfunction "RESERVED_3") (pintype "passive"))
      (node (ref "U9") (pin "6") (pinfunction "VS_6") (pintype "passive"))
    )
    (net (code "81") (name "Net-(U10-C1+)") (class "Default")
      (node (ref "C31") (pin "2") (pintype "passive"))
      (node (ref "U10") (pin "1") (pinfunction "C1+_1") (pintype "passive"))
    )
    (net (code "82") (name "Net-(U10-C1-)") (class "Default")
      (node (ref "C31") (pin "1") (pintype "passive"))
      (node (ref "U10") (pin "3") (pinfunction "C1-_3") (pintype "passive"))
    )
    (net (code "83") (name "Net-(U10-C2+)") (class "Default")
      (node (ref "C32") (pin "2") (pintype "passive"))
      (node (ref "U10") (pin "4") (pinfunction "C2+_4") (pintype "passive"))
    )
    (net (code "84") (name "Net-(U10-C2-)") (class "Default")
      (node (ref "C32") (pin "1") (pintype "passive"))
      (node (ref "U10") (pin "5") (pinfunction "C2-_5") (pintype "passive"))
    )
    (net (code "85") (name "Net-(U10-V+)") (class "Default")
      (node (ref "C30") (pin "1") (pintype "passive"))
      (node (ref "U10") (pin "2") (pinfunction "V+_2") (pintype "passive"))
    )
    (net (code "86") (name "Net-(U10-V-)") (class "Default")
      (node (ref "C33") (pin "2") (pintype "passive"))
      (node (ref "U10") (pin "6") (pinfunction "V-_6") (pintype "passive"))
    )
    (net (code "87") (name "PYRO_GND") (class "Default")
      (node (ref "D11") (pin "2") (pinfunction "2_2") (pintype "power_in"))
      (node (ref "D15") (pin "A") (pinfunction "1_A") (pintype "passive"))
      (node (ref "D5") (pin "2") (pinfunction "2_2") (pintype "power_in"))
      (node (ref "J3") (pin "2") (pinfunction "2_2") (pintype "passive"))
      (node (ref "Q1") (pin "S") (pintype "passive"))
      (node (ref "Q4") (pin "S") (pintype "passive"))
      (node (ref "R13") (pin "1") (pintype "passive"))
      (node (ref "R22") (pin "1") (pintype "passive"))
    )
    (net (code "88") (name "PYRO_VCC") (class "Default")
      (node (ref "D10") (pin "K") (pinfunction "2_K") (pintype "passive"))
      (node (ref "D2") (pin "K") (pinfunction "2_K") (pintype "passive"))
      (node (ref "D4") (pin "K") (pinfunction "2_K") (pintype "passive"))
      (node (ref "J1") (pin "1") (pinfunction "1_1") (pintype "passive"))
      (node (ref "J4") (pin "1") (pinfunction "1_1") (pintype "passive"))
      (node (ref "U3") (pin "4") (pinfunction "KOLLEKTÖR_4") (pintype "passive"))
      (node (ref "U4") (pin "4") (pinfunction "KOLLEKTÖR_4") (pintype "passive"))
    )
    (net (code "89") (name "PYRO_VCC_IN") (class "Default")
      (node (ref "D15") (pin "K") (pinfunction "2_K") (pintype "passive"))
      (node (ref "D2") (pin "A") (pinfunction "1_A") (pintype "passive"))
      (node (ref "J3") (pin "1") (pinfunction "1_1") (pintype "passive"))
    )
    (net (code "90") (name "VBAT") (class "Default")
      (node (ref "D16") (pin "K") (pinfunction "2_K") (pintype "passive"))
      (node (ref "D7") (pin "A") (pinfunction "1_A") (pintype "passive"))
      (node (ref "J2") (pin "1") (pinfunction "1_1") (pintype "passive"))
    )
    (net (code "91") (name "VBUS") (class "Default")
      (node (ref "C20") (pin "2") (pintype "passive"))
      (node (ref "C21") (pin "2") (pintype "passive"))
      (node (ref "FB2") (pin "1") (pinfunction "1_1") (pintype "passive"))
      (node (ref "J5") (pin "A4/B9") (pinfunction "VBUS_A4/B9") (pintype "passive"))
      (node (ref "J5") (pin "B4/A9") (pinfunction "VBUS_B4/A9") (pintype "passive"))
      (node (ref "U7") (pin "5") (pinfunction "VBUS_5") (pintype "passive"))
    )
    (net (code "92") (name "VIN") (class "Default")
      (node (ref "C6") (pin "2") (pintype "passive"))
      (node (ref "C7") (pin "2") (pintype "passive"))
      (node (ref "D7") (pin "K") (pinfunction "2_K") (pintype "passive"))
      (node (ref "D9") (pin "K") (pinfunction "2_K") (pintype "passive"))
      (node (ref "U1") (pin "2") (pinfunction "VIN_2") (pintype "passive"))
      (node (ref "U1") (pin "3") (pinfunction "EN_3") (pintype "passive"))
    )
    (net (code "93") (name "unconnected-(J5-PadNC)") (class "Default")
      (node (ref "J5") (pin "NC") (pinfunction "NC_NC") (pintype "passive+no_connect"))
    )
    (net (code "94") (name "unconnected-(J5-SBU1-PadA8)") (class "Default")
      (node (ref "J5") (pin "A8") (pinfunction "SBU1_A8") (pintype "passive+no_connect"))
    )
    (net (code "95") (name "unconnected-(J5-SBU2-PadB8)") (class "Default")
      (node (ref "J5") (pin "B8") (pinfunction "SBU2_B8") (pintype "passive+no_connect"))
    )
    (net (code "96") (name "unconnected-(J6-CD-Pad1)") (class "Default")
      (node (ref "J6") (pin "1") (pinfunction "CD_1") (pintype "passive+no_connect"))
    )
    (net (code "97") (name "unconnected-(J6-CTS-Pad7)") (class "Default")
      (node (ref "J6") (pin "7") (pinfunction "CTS_7") (pintype "passive+no_connect"))
    )
    (net (code "98") (name "unconnected-(J6-DSR-Pad6)") (class "Default")
      (node (ref "J6") (pin "6") (pinfunction "DSR_6") (pintype "passive+no_connect"))
    )
    (net (code "99") (name "unconnected-(J6-DTR-Pad4)") (class "Default")
      (node (ref "J6") (pin "4") (pinfunction "DTR_4") (pintype "passive+no_connect"))
    )
    (net (code "100") (name "unconnected-(J6-RI-Pad9)") (class "Default")
      (node (ref "J6") (pin "9") (pinfunction "RI_9") (pintype "passive+no_connect"))
    )
    (net (code "101") (name "unconnected-(J6-RTS-Pad8)") (class "Default")
      (node (ref "J6") (pin "8") (pinfunction "RTS_8") (pintype "passive+no_connect"))
    )
    (net (code "102") (name "unconnected-(LS1-NC-Pad3)") (class "Default")
      (node (ref "LS1") (pin "3") (pinfunction "NC_3") (pintype "passive+no_connect"))
    )
    (net (code "103") (name "unconnected-(LS1-NC-Pad4)") (class "Default")
      (node (ref "LS1") (pin "4") (pinfunction "NC_4") (pintype "passive+no_connect"))
    )
    (net (code "104") (name "unconnected-(U2-AADET_N-Pad8)") (class "Default")
      (node (ref "U2") (pin "8") (pinfunction "AADET_N_8") (pintype "passive+no_connect"))
    )
    (net (code "105") (name "unconnected-(U2-EX_ANT-Pad11)") (class "Default")
      (node (ref "U2") (pin "11") (pinfunction "EX_ANT_11") (pintype "passive+no_connect"))
    )
    (net (code "106") (name "unconnected-(U2-FORCE_ON-Pad7)") (class "Default")
      (node (ref "U2") (pin "7") (pinfunction "FORCE_ON_7") (pintype "passive+no_connect"))
    )
    (net (code "107") (name "unconnected-(U2-NC-Pad9)") (class "Default")
      (node (ref "U2") (pin "9") (pinfunction "NC_9") (pintype "passive+no_connect"))
    )
    (net (code "108") (name "unconnected-(U5-AUX_CL-Pad7)") (class "Default")
      (node (ref "U5") (pin "7") (pinfunction "AUX_CL_7") (pintype "passive+no_connect"))
    )
    (net (code "109") (name "unconnected-(U5-AUX_DA-Pad21)") (class "Default")
      (node (ref "U5") (pin "21") (pinfunction "AUX_DA_21") (pintype "passive+no_connect"))
    )
    (net (code "110") (name "unconnected-(U5-INT-Pad12)") (class "Default")
      (node (ref "U5") (pin "12") (pinfunction "INT_12") (pintype "passive+no_connect"))
    )
    (net (code "111") (name "unconnected-(U5-NC-Pad2)") (class "Default")
      (node (ref "U5") (pin "2") (pinfunction "NC_2") (pintype "passive+no_connect"))
    )
    (net (code "112") (name "unconnected-(U5-NC-Pad3)") (class "Default")
      (node (ref "U5") (pin "3") (pinfunction "NC_3") (pintype "passive+no_connect"))
    )
    (net (code "113") (name "unconnected-(U5-NC-Pad4)") (class "Default")
      (node (ref "U5") (pin "4") (pinfunction "NC_4") (pintype "passive+no_connect"))
    )
    (net (code "114") (name "unconnected-(U5-NC-Pad5)") (class "Default")
      (node (ref "U5") (pin "5") (pinfunction "NC_5") (pintype "passive+no_connect"))
    )
    (net (code "115") (name "unconnected-(U5-NC-Pad6)") (class "Default")
      (node (ref "U5") (pin "6") (pinfunction "NC_6") (pintype "passive+no_connect"))
    )
    (net (code "116") (name "unconnected-(U5-NC-Pad14)") (class "Default")
      (node (ref "U5") (pin "14") (pinfunction "NC_14") (pintype "passive+no_connect"))
    )
    (net (code "117") (name "unconnected-(U5-NC-Pad15)") (class "Default")
      (node (ref "U5") (pin "15") (pinfunction "NC_15") (pintype "passive+no_connect"))
    )
    (net (code "118") (name "unconnected-(U5-NC-Pad16)") (class "Default")
      (node (ref "U5") (pin "16") (pinfunction "NC_16") (pintype "passive+no_connect"))
    )
    (net (code "119") (name "unconnected-(U5-NC-Pad17)") (class "Default")
      (node (ref "U5") (pin "17") (pinfunction "NC_17") (pintype "passive+no_connect"))
    )
    (net (code "120") (name "unconnected-(U5-RESV-Pad19)") (class "Default")
      (node (ref "U5") (pin "19") (pinfunction "RESV_19") (pintype "passive+no_connect"))
    )
    (net (code "121") (name "unconnected-(U6-IO4-Pad4)") (class "Default")
      (node (ref "U6") (pin "4") (pinfunction "IO4_4") (pintype "passive"))
    )
    (net (code "122") (name "unconnected-(U6-IO7-Pad7)") (class "Default")
      (node (ref "U6") (pin "7") (pinfunction "IO7_7") (pintype "passive"))
    )
    (net (code "123") (name "unconnected-(U6-IO8-Pad12)") (class "Default")
      (node (ref "U6") (pin "12") (pinfunction "IO8_12") (pintype "passive"))
    )
    (net (code "124") (name "unconnected-(U6-IO15-Pad8)") (class "Default")
      (node (ref "U6") (pin "8") (pinfunction "IO15_8") (pintype "passive"))
    )
    (net (code "125") (name "unconnected-(U6-IO35-Pad28)") (class "Default")
      (node (ref "U6") (pin "28") (pinfunction "IO35_28") (pintype "passive"))
    )
    (net (code "126") (name "unconnected-(U6-IO36-Pad29)") (class "Default")
      (node (ref "U6") (pin "29") (pinfunction "IO36_29") (pintype "passive"))
    )
    (net (code "127") (name "unconnected-(U6-IO37-Pad30)") (class "Default")
      (node (ref "U6") (pin "30") (pinfunction "IO37_30") (pintype "passive"))
    )
    (net (code "128") (name "unconnected-(U6-IO40-Pad33)") (class "Default")
      (node (ref "U6") (pin "33") (pinfunction "IO40_33") (pintype "passive"))
    )
    (net (code "129") (name "unconnected-(U6-IO45-Pad26)") (class "Default")
      (node (ref "U6") (pin "26") (pinfunction "IO45_26") (pintype "passive"))
    )
    (net (code "130") (name "unconnected-(U8-SDO-Pad6)") (class "Default")
      (node (ref "U8") (pin "6") (pinfunction "SDO_6") (pintype "passive+no_connect"))
    )
    (net (code "131") (name "unconnected-(U9-INT1-Pad8)") (class "Default")
      (node (ref "U9") (pin "8") (pinfunction "INT1_8") (pintype "passive+no_connect"))
    )
    (net (code "132") (name "unconnected-(U9-INT2-Pad9)") (class "Default")
      (node (ref "U9") (pin "9") (pinfunction "INT2_9") (pintype "passive+no_connect"))
    )
    (net (code "133") (name "unconnected-(U9-NC-Pad10)") (class "Default")
      (node (ref "U9") (pin "10") (pinfunction "NC_10") (pintype "passive+no_connect"))
    )
    (net (code "134") (name "unconnected-(U10-DIN2-Pad10)") (class "Default")
      (node (ref "U10") (pin "10") (pinfunction "DIN2_10") (pintype "passive+no_connect"))
    )
    (net (code "135") (name "unconnected-(U10-DOUT2-Pad7)") (class "Default")
      (node (ref "U10") (pin "7") (pinfunction "DOUT2_7") (pintype "passive+no_connect"))
    )
    (net (code "136") (name "unconnected-(U10-RIN2-Pad8)") (class "Default")
      (node (ref "U10") (pin "8") (pinfunction "RIN2_8") (pintype "passive+no_connect"))
    )
    (net (code "137") (name "unconnected-(U10-ROUT2-Pad9)") (class "Default")
      (node (ref "U10") (pin "9") (pinfunction "ROUT2_9") (pintype "passive+no_connect"))
    )
    (net (code "138") (name "unconnected-(U11-ANT-Pad21)") (class "Default")
      (node (ref "U11") (pin "21") (pinfunction "ANT_21") (pintype "passive+no_connect"))
    )
    (net (code "139") (name "unconnected-(U11-DIO2-Pad8)") (class "Default")
      (node (ref "U11") (pin "8") (pinfunction "DIO2_8") (pintype "passive+no_connect"))
    )
  )
)
